# stm32H7_board_rev8_144_16.net
KiCad netlist of a schematic drawn in EAGLE
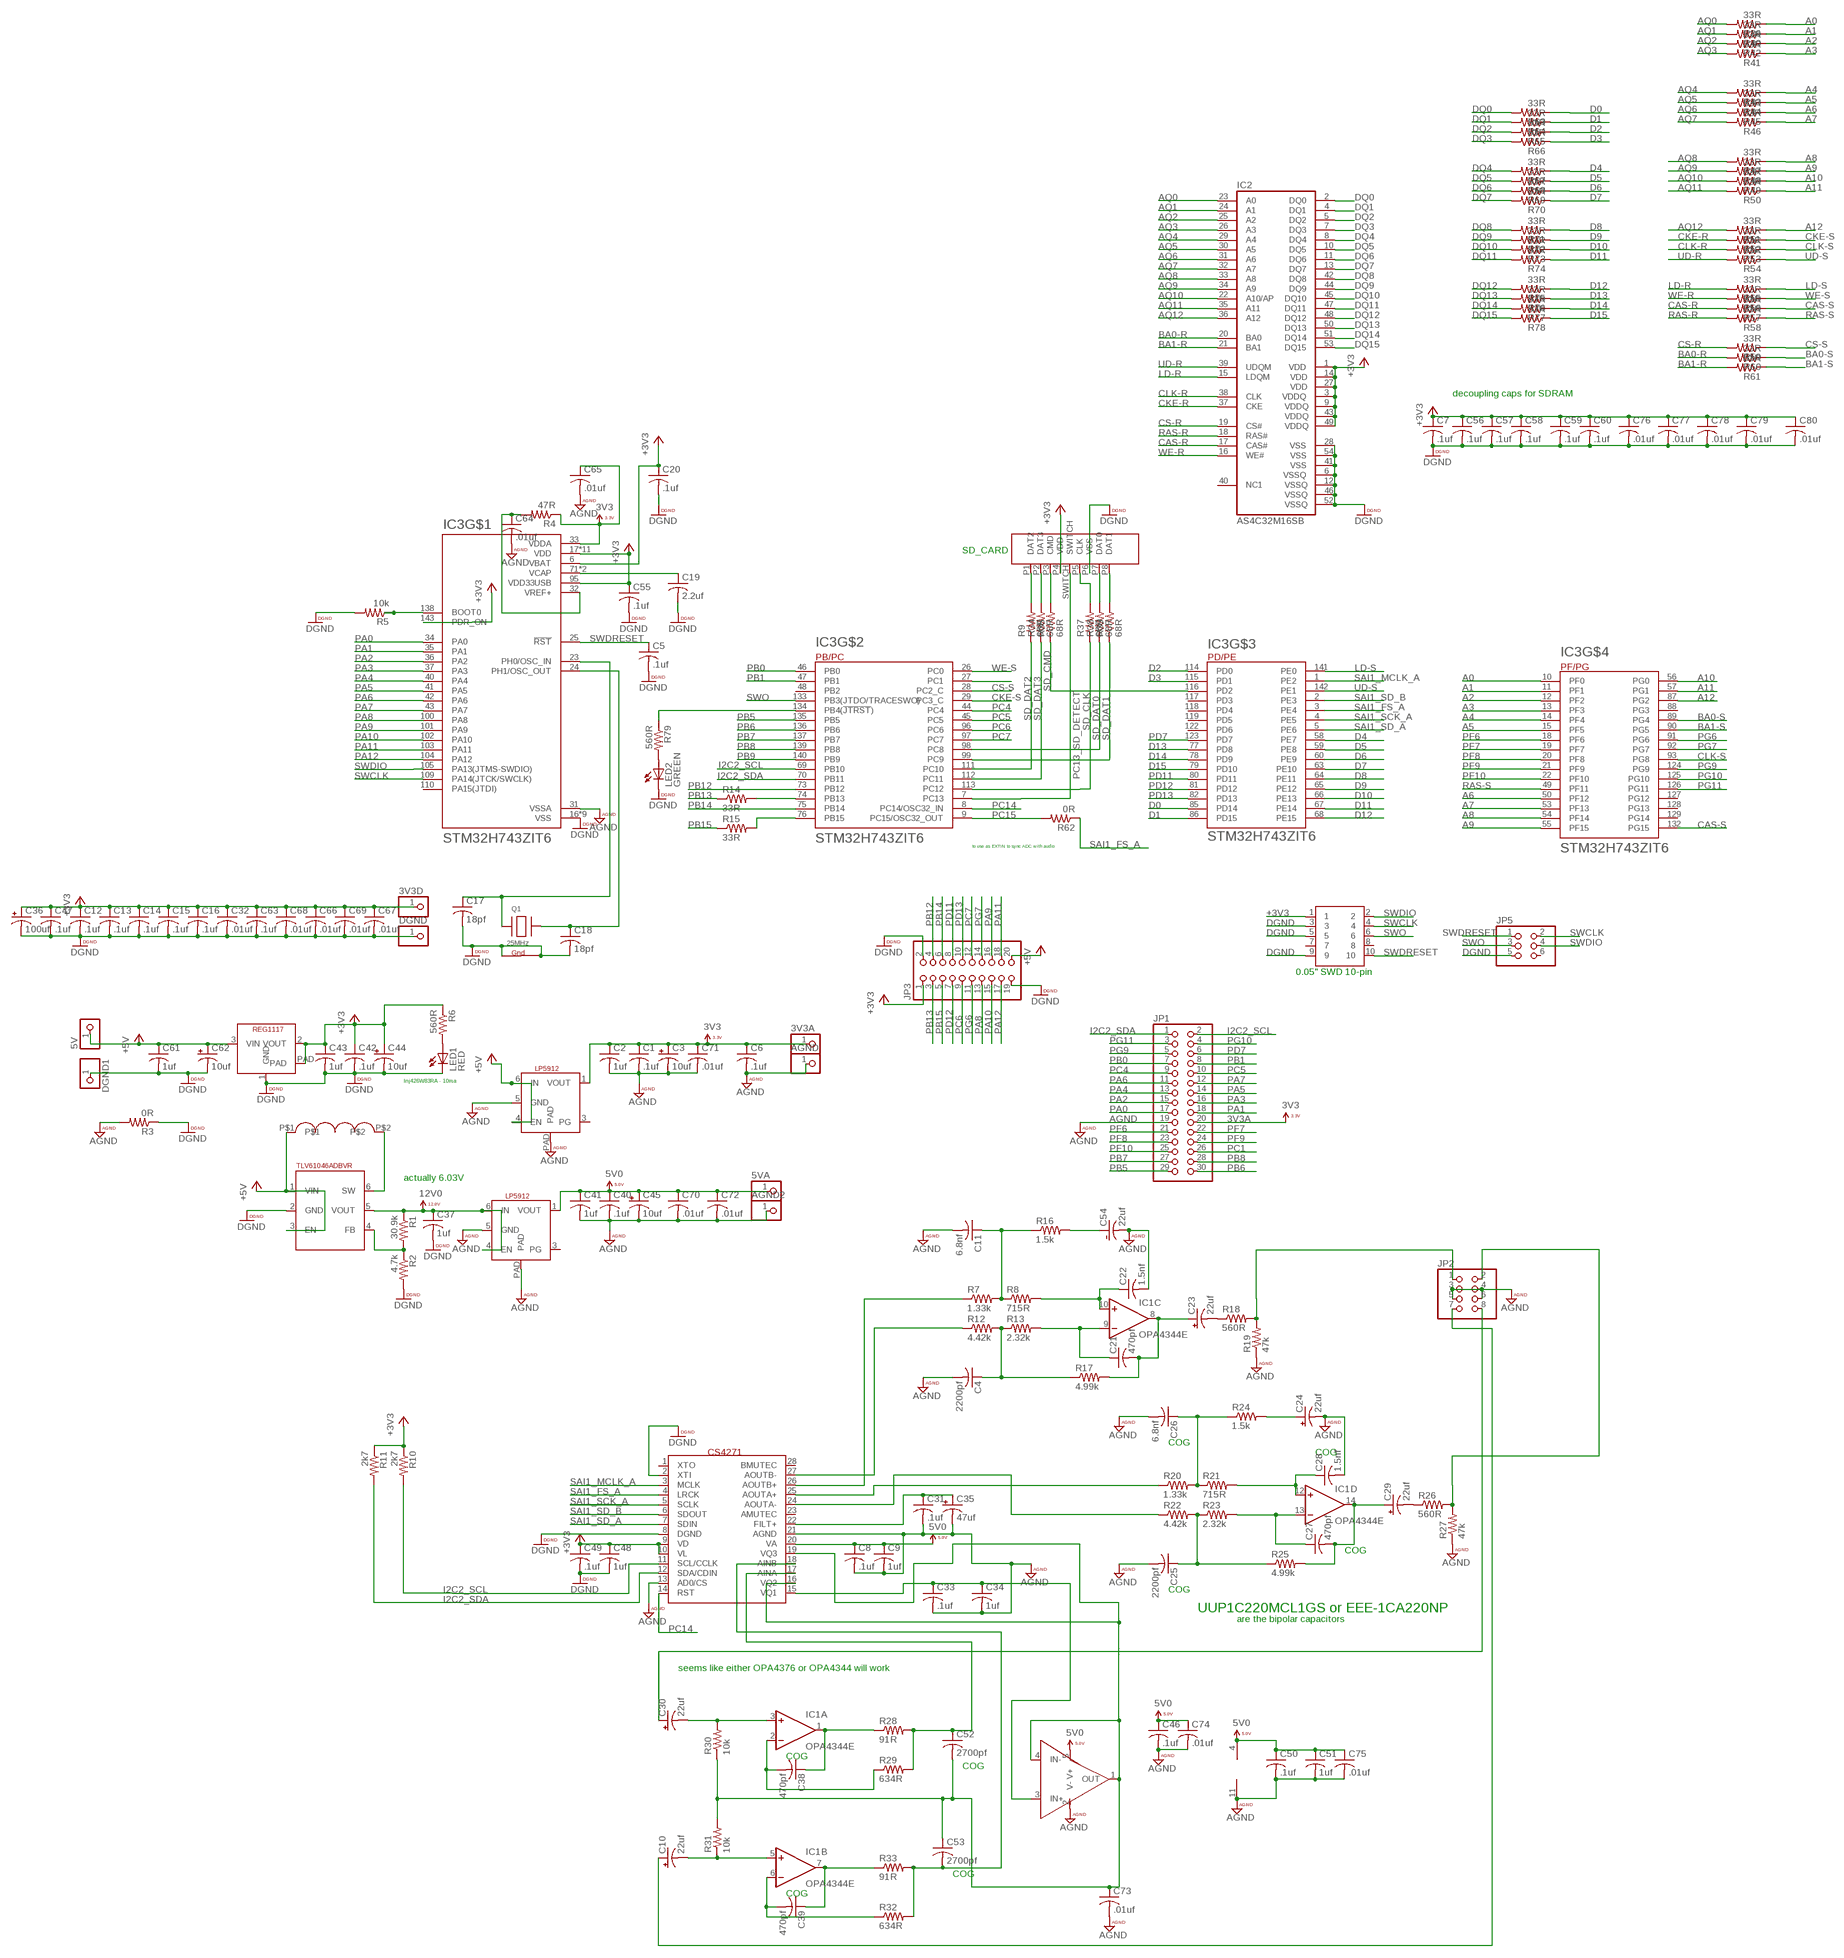
[diagram p0: schematic, sheet 1]

(export (version "E")
  (design (tool "Eeschema 10.0.6"))
  (components
    (comp (ref "3V3A")
      (value "PINHD-1X1")
      (footprint "eagle-import:1X01")
      (fields (field (name "PARTNO") "*DNP"))
      (libsource (lib "eagle-import") (part "PINHD-1X1"))
    )
    (comp (ref "3V3D")
      (value "PINHD-1X1")
      (footprint "eagle-import:1X01")
      (fields (field (name "PARTNO") "*DNP"))
      (libsource (lib "eagle-import") (part "PINHD-1X1"))
    )
    (comp (ref "5V")
      (value "PINHD-1X1")
      (footprint "eagle-import:1X01")
      (fields (field (name "PARTNO") "*DNP"))
      (libsource (lib "eagle-import") (part "PINHD-1X1"))
    )
    (comp (ref "5VA")
      (value "PINHD-1X1")
      (footprint "eagle-import:1X01")
      (fields (field (name "PARTNO") "*DNP"))
      (libsource (lib "eagle-import") (part "PINHD-1X1"))
    )
    (comp (ref "AGND")
      (value "PINHD-1X1")
      (footprint "eagle-import:1X01")
      (fields (field (name "PARTNO") "*DNP"))
      (libsource (lib "eagle-import") (part "PINHD-1X1"))
    )
    (comp (ref "AGND2")
      (value "PINHD-1X1")
      (footprint "eagle-import:1X01")
      (fields (field (name "PARTNO") "*DNP"))
      (libsource (lib "eagle-import") (part "PINHD-1X1"))
    )
    (comp (ref "C1")
      (value ".1uf")
      (footprint "eagle-import:C0603")
      (fields (field (name "PARTNO") "CC0603KRX7R8BB104"))
      (libsource (lib "eagle-import") (part "rcl_C-USC0603"))
    )
    (comp (ref "C2")
      (value "1uf")
      (footprint "eagle-import:C1206")
      (fields (field (name "PARTNO") "C3216X7R1E105K085AA"))
      (libsource (lib "eagle-import") (part "rcl_C-USC1206"))
    )
    (comp (ref "C3")
      (value "10uf")
      (footprint "eagle-import:SMC_B")
      (fields (field (name "PARTNO") "TAJB106K025RNJ"))
      (libsource (lib "eagle-import") (part "CPOL-USSMCB"))
    )
    (comp (ref "C4")
      (value "2200pf")
      (footprint "eagle-import:C0603")
      (fields (field (name "PARTNO") "CC0603JRNPO9BN221"))
      (libsource (lib "eagle-import") (part "rcl_C-USC0603"))
    )
    (comp (ref "C5")
      (value ".1uf")
      (footprint "eagle-import:C0402")
      (fields (field (name "PARTNO") "CC0402KRX7R8BB104"))
      (libsource (lib "eagle-import") (part "rcl_C-USC0402"))
    )
    (comp (ref "C6")
      (value ".1uf")
      (footprint "eagle-import:C0402")
      (fields (field (name "PARTNO") "CC0402KRX7R8BB104"))
      (libsource (lib "eagle-import") (part "rcl_C-USC0402"))
    )
    (comp (ref "C7")
      (value ".1uf")
      (footprint "eagle-import:C0402")
      (fields (field (name "PARTNO") "CC0402KRX7R8BB104"))
      (libsource (lib "eagle-import") (part "rcl_C-USC0402"))
    )
    (comp (ref "C8")
      (value ".1uf")
      (footprint "eagle-import:C0603")
      (fields (field (name "PARTNO") "CC0603KRX7R8BB104"))
      (libsource (lib "eagle-import") (part "rcl_C-USC0603"))
    )
    (comp (ref "C9")
      (value "1uf")
      (footprint "eagle-import:C1206")
      (fields (field (name "PARTNO") "C3216X7R1E105K085AA"))
      (libsource (lib "eagle-import") (part "rcl_C-USC1206"))
    )
    (comp (ref "C10")
      (value "22uf")
      (footprint "eagle-import:PANASONIC_D")
      (fields (field (name "PARTNO") "EEE-1CA220NP"))
      (libsource (lib "eagle-import") (part "CPOL-USD"))
    )
    (comp (ref "C11")
      (value "6.8nf")
      (footprint "eagle-import:C0603")
      (fields (field (name "PARTNO") "C0603C682J5GACTU"))
      (libsource (lib "eagle-import") (part "rcl_C-USC0603"))
    )
    (comp (ref "C12")
      (value ".1uf")
      (footprint "eagle-import:C0402")
      (fields (field (name "PARTNO") "CC0402KRX7R8BB104"))
      (libsource (lib "eagle-import") (part "rcl_C-USC0402"))
    )
    (comp (ref "C13")
      (value ".1uf")
      (footprint "eagle-import:C0402")
      (fields (field (name "PARTNO") "CC0402KRX7R8BB104"))
      (libsource (lib "eagle-import") (part "rcl_C-USC0402"))
    )
    (comp (ref "C14")
      (value ".1uf")
      (footprint "eagle-import:C0402")
      (fields (field (name "PARTNO") "CC0402KRX7R8BB104"))
      (libsource (lib "eagle-import") (part "rcl_C-USC0402"))
    )
    (comp (ref "C15")
      (value ".1uf")
      (footprint "eagle-import:C0402")
      (fields (field (name "PARTNO") "CC0402KRX7R8BB104"))
      (libsource (lib "eagle-import") (part "rcl_C-USC0402"))
    )
    (comp (ref "C16")
      (value ".1uf")
      (footprint "eagle-import:C0402")
      (fields (field (name "PARTNO") "CC0402KRX7R8BB104"))
      (libsource (lib "eagle-import") (part "rcl_C-USC0402"))
    )
    (comp (ref "C17")
      (value "18pf")
      (footprint "eagle-import:C0603")
      (fields (field (name "PARTNO") "CL10C180JB8NNNC"))
      (libsource (lib "eagle-import") (part "rcl_C-USC0603"))
    )
    (comp (ref "C18")
      (value "18pf")
      (footprint "eagle-import:C0603")
      (fields (field (name "PARTNO") "CL10C180JB8NNNC"))
      (libsource (lib "eagle-import") (part "rcl_C-USC0603"))
    )
    (comp (ref "C19")
      (value "2.2uf")
      (footprint "eagle-import:C1206")
      (fields (field (name "PARTNO") "T491A225K020AT"))
      (libsource (lib "eagle-import") (part "C-USC1206"))
    )
    (comp (ref "C20")
      (value ".1uf")
      (footprint "eagle-import:C0402")
      (fields (field (name "PARTNO") "CC0402KRX7R8BB104"))
      (libsource (lib "eagle-import") (part "rcl_C-USC0402"))
    )
    (comp (ref "C21")
      (value "470pf")
      (footprint "eagle-import:C0603")
      (fields (field (name "PARTNO") "CC0603JRNPO9BN471"))
      (libsource (lib "eagle-import") (part "rcl_C-USC0603"))
    )
    (comp (ref "C22")
      (value "1.5nf")
      (footprint "eagle-import:C0603")
      (fields (field (name "PARTNO") "C0603C152J5GACTU"))
      (libsource (lib "eagle-import") (part "rcl_C-USC0603"))
    )
    (comp (ref "C23")
      (value "22uf")
      (footprint "eagle-import:PANASONIC_D")
      (fields (field (name "PARTNO") "EEE-1CA220NP"))
      (libsource (lib "eagle-import") (part "CPOL-USD"))
    )
    (comp (ref "C24")
      (value "22uf")
      (footprint "eagle-import:PANASONIC_D")
      (fields (field (name "PARTNO") "EEE-1CA220NP"))
      (libsource (lib "eagle-import") (part "CPOL-USD"))
    )
    (comp (ref "C25")
      (value "2200pf")
      (footprint "eagle-import:C0603")
      (fields (field (name "PARTNO") "CC0603JRNPO9BN221"))
      (libsource (lib "eagle-import") (part "rcl_C-USC0603"))
    )
    (comp (ref "C26")
      (value "6.8nf")
      (footprint "eagle-import:C0603")
      (fields (field (name "PARTNO") "C0603C682J5GACTU"))
      (libsource (lib "eagle-import") (part "rcl_C-USC0603"))
    )
    (comp (ref "C27")
      (value "470pf")
      (footprint "eagle-import:C0603")
      (fields (field (name "PARTNO") "CC0603JRNPO9BN471"))
      (libsource (lib "eagle-import") (part "rcl_C-USC0603"))
    )
    (comp (ref "C28")
      (value "1.5nf")
      (footprint "eagle-import:C0603")
      (fields (field (name "PARTNO") "C0603C152J5GACTU"))
      (libsource (lib "eagle-import") (part "rcl_C-USC0603"))
    )
    (comp (ref "C29")
      (value "22uf")
      (footprint "eagle-import:PANASONIC_D")
      (fields (field (name "PARTNO") "EEE-1CA220NP"))
      (libsource (lib "eagle-import") (part "CPOL-USD"))
    )
    (comp (ref "C30")
      (value "22uf")
      (footprint "eagle-import:PANASONIC_D")
      (fields (field (name "PARTNO") "EEE-1CA220NP"))
      (libsource (lib "eagle-import") (part "CPOL-USD"))
    )
    (comp (ref "C31")
      (value ".1uf")
      (footprint "eagle-import:C0603")
      (fields (field (name "PARTNO") "CC0603KRX7R8BB104"))
      (libsource (lib "eagle-import") (part "rcl_C-USC0603"))
    )
    (comp (ref "C32")
      (value ".01uf")
      (footprint "eagle-import:C0402")
      (fields (field (name "PARTNO") "CC0402KRX7R8BB103"))
      (libsource (lib "eagle-import") (part "rcl_C-USC0402"))
    )
    (comp (ref "C33")
      (value ".1uf")
      (footprint "eagle-import:C0603")
      (fields (field (name "PARTNO") "CC0603KRX7R8BB104"))
      (libsource (lib "eagle-import") (part "rcl_C-USC0603"))
    )
    (comp (ref "C34")
      (value "1uf")
      (footprint "eagle-import:C1206")
      (fields (field (name "PARTNO") "C3216X7R1E105K085AA"))
      (libsource (lib "eagle-import") (part "rcl_C-USC1206"))
    )
    (comp (ref "C35")
      (value "47uf")
      (footprint "eagle-import:PANASONIC_D")
      (fields (field (name "PARTNO") "EEE-1CA470AP"))
      (libsource (lib "eagle-import") (part "CPOL-USD"))
    )
    (comp (ref "C36")
      (value "100uf")
      (footprint "eagle-import:PANASONIC_E")
      (fields (field (name "PARTNO") "EEE-1CA101AP"))
      (libsource (lib "eagle-import") (part "CPOL-USE"))
    )
    (comp (ref "C37")
      (value "1uf")
      (footprint "eagle-import:C1206")
      (fields (field (name "PARTNO") "C3216X7R1E105K085AA"))
      (libsource (lib "eagle-import") (part "rcl_C-USC1206"))
    )
    (comp (ref "C38")
      (value "470pf")
      (footprint "eagle-import:C0603")
      (fields (field (name "PARTNO") "CC0603JRNPO9BN471"))
      (libsource (lib "eagle-import") (part "rcl_C-USC0603"))
    )
    (comp (ref "C39")
      (value "470pf")
      (footprint "eagle-import:C0603")
      (fields (field (name "PARTNO") "CC0603JRNPO9BN471"))
      (libsource (lib "eagle-import") (part "rcl_C-USC0603"))
    )
    (comp (ref "C40")
      (value ".1uf")
      (footprint "eagle-import:C0603")
      (fields (field (name "PARTNO") "CC0603KRX7R8BB104"))
      (libsource (lib "eagle-import") (part "rcl_C-USC0603"))
    )
    (comp (ref "C41")
      (value "1uf")
      (footprint "eagle-import:C1206")
      (fields (field (name "PARTNO") "C3216X7R1E105K085AA"))
      (libsource (lib "eagle-import") (part "rcl_C-USC1206"))
    )
    (comp (ref "C42")
      (value ".1uf")
      (footprint "eagle-import:C0603")
      (fields (field (name "PARTNO") "CC0603KRX7R8BB104"))
      (libsource (lib "eagle-import") (part "rcl_C-USC0603"))
    )
    (comp (ref "C43")
      (value "1uf")
      (footprint "eagle-import:C1206")
      (fields (field (name "PARTNO") "C3216X7R1E105K085AA"))
      (libsource (lib "eagle-import") (part "rcl_C-USC1206"))
    )
    (comp (ref "C44")
      (value "10uf")
      (footprint "eagle-import:SMC_B")
      (fields (field (name "PARTNO") "TAJB106K025RNJ"))
      (libsource (lib "eagle-import") (part "CPOL-USSMCB"))
    )
    (comp (ref "C45")
      (value "10uf")
      (footprint "eagle-import:SMC_B")
      (fields (field (name "PARTNO") "TAJB106K025RNJ"))
      (libsource (lib "eagle-import") (part "CPOL-USSMCB"))
    )
    (comp (ref "C46")
      (value ".1uf")
      (footprint "eagle-import:C0603")
      (fields (field (name "PARTNO") "CC0603KRX7R8BB104"))
      (libsource (lib "eagle-import") (part "rcl_C-USC0603"))
    )
    (comp (ref "C47")
      (value ".1uf")
      (footprint "eagle-import:C0402")
      (fields (field (name "PARTNO") "CC0402KRX7R8BB104"))
      (libsource (lib "eagle-import") (part "rcl_C-USC0402"))
    )
    (comp (ref "C48")
      (value "1uf")
      (footprint "eagle-import:C1206")
      (fields (field (name "PARTNO") "C3216X7R1E105K085AA"))
      (libsource (lib "eagle-import") (part "rcl_C-USC1206"))
    )
    (comp (ref "C49")
      (value ".1uf")
      (footprint "eagle-import:C0603")
      (fields (field (name "PARTNO") "CC0603KRX7R8BB104"))
      (libsource (lib "eagle-import") (part "rcl_C-USC0603"))
    )
    (comp (ref "C50")
      (value ".1uf")
      (footprint "eagle-import:C0603")
      (fields (field (name "PARTNO") "CC0603KRX7R8BB104"))
      (libsource (lib "eagle-import") (part "rcl_C-USC0603"))
    )
    (comp (ref "C51")
      (value "1uf")
      (footprint "eagle-import:C1206")
      (fields (field (name "PARTNO") "C3216X7R1E105K085AA"))
      (libsource (lib "eagle-import") (part "rcl_C-USC1206"))
    )
    (comp (ref "C52")
      (value "2700pf")
      (footprint "eagle-import:C0603")
      (fields (field (name "PARTNO") "C0603C272J5GACTU"))
      (libsource (lib "eagle-import") (part "rcl_C-USC0603"))
    )
    (comp (ref "C53")
      (value "2700pf")
      (footprint "eagle-import:C0603")
      (fields (field (name "PARTNO") "C0603C272J5GACTU"))
      (libsource (lib "eagle-import") (part "rcl_C-USC0603"))
    )
    (comp (ref "C54")
      (value "22uf")
      (footprint "eagle-import:PANASONIC_D")
      (fields (field (name "PARTNO") "EEE-1CA220NP"))
      (libsource (lib "eagle-import") (part "CPOL-USD"))
    )
    (comp (ref "C55")
      (value ".1uf")
      (footprint "eagle-import:C0402")
      (fields (field (name "PARTNO") "CC0402KRX7R8BB104"))
      (libsource (lib "eagle-import") (part "rcl_C-USC0402"))
    )
    (comp (ref "C56")
      (value ".1uf")
      (footprint "eagle-import:C0402")
      (fields (field (name "PARTNO") "CC0402KRX7R8BB104"))
      (libsource (lib "eagle-import") (part "rcl_C-USC0402"))
    )
    (comp (ref "C57")
      (value ".1uf")
      (footprint "eagle-import:C0402")
      (fields (field (name "PARTNO") "CC0402KRX7R8BB104"))
      (libsource (lib "eagle-import") (part "rcl_C-USC0402"))
    )
    (comp (ref "C58")
      (value ".1uf")
      (footprint "eagle-import:C0402")
      (fields (field (name "PARTNO") "CC0402KRX7R8BB104"))
      (libsource (lib "eagle-import") (part "rcl_C-USC0402"))
    )
    (comp (ref "C59")
      (value ".1uf")
      (footprint "eagle-import:C0402")
      (fields (field (name "PARTNO") "CC0402KRX7R8BB104"))
      (libsource (lib "eagle-import") (part "rcl_C-USC0402"))
    )
    (comp (ref "C60")
      (value ".1uf")
      (footprint "eagle-import:C0402")
      (fields (field (name "PARTNO") "CC0402KRX7R8BB104"))
      (libsource (lib "eagle-import") (part "rcl_C-USC0402"))
    )
    (comp (ref "C61")
      (value "1uf")
      (footprint "eagle-import:C1206")
      (fields (field (name "PARTNO") "C3216X7R1E105K085AA"))
      (libsource (lib "eagle-import") (part "rcl_C-USC1206"))
    )
    (comp (ref "C62")
      (value "10uf")
      (footprint "eagle-import:SMC_B")
      (fields (field (name "PARTNO") "TAJB106K025RNJ"))
      (libsource (lib "eagle-import") (part "CPOL-USSMCB"))
    )
    (comp (ref "C63")
      (value ".1uf")
      (footprint "eagle-import:C0402")
      (fields (field (name "PARTNO") "CC0402KRX7R8BB104"))
      (libsource (lib "eagle-import") (part "rcl_C-USC0402"))
    )
    (comp (ref "C64")
      (value ".01uf")
      (footprint "eagle-import:C0402")
      (fields (field (name "PARTNO") "CC0402KRX7R8BB103"))
      (libsource (lib "eagle-import") (part "rcl_C-USC0402"))
    )
    (comp (ref "C65")
      (value ".01uf")
      (footprint "eagle-import:C0402")
      (fields (field (name "PARTNO") "CC0402KRX7R8BB103"))
      (libsource (lib "eagle-import") (part "rcl_C-USC0402"))
    )
    (comp (ref "C66")
      (value ".01uf")
      (footprint "eagle-import:C0201")
      (fields (field (name "PARTNO") "TMK063B7103KP-F"))
      (libsource (lib "eagle-import") (part "C-USC0201"))
    )
    (comp (ref "C67")
      (value ".01uf")
      (footprint "eagle-import:C0201")
      (fields (field (name "PARTNO") "TMK063B7103KP-F"))
      (libsource (lib "eagle-import") (part "C-USC0201"))
    )
    (comp (ref "C68")
      (value ".01uf")
      (footprint "eagle-import:C0201")
      (fields (field (name "PARTNO") "TMK063B7103KP-F"))
      (libsource (lib "eagle-import") (part "C-USC0201"))
    )
    (comp (ref "C69")
      (value ".01uf")
      (footprint "eagle-import:C0201")
      (fields (field (name "PARTNO") "TMK063B7103KP-F"))
      (libsource (lib "eagle-import") (part "C-USC0201"))
    )
    (comp (ref "C70")
      (value ".01uf")
      (footprint "eagle-import:C0201")
      (fields (field (name "PARTNO") "TMK063B7103KP-F"))
      (libsource (lib "eagle-import") (part "C-USC0201"))
    )
    (comp (ref "C71")
      (value ".01uf")
      (footprint "eagle-import:C0201")
      (fields (field (name "PARTNO") "TMK063B7103KP-F"))
      (libsource (lib "eagle-import") (part "C-USC0201"))
    )
    (comp (ref "C72")
      (value ".01uf")
      (footprint "eagle-import:C0201")
      (fields (field (name "PARTNO") "TMK063B7103KP-F"))
      (libsource (lib "eagle-import") (part "C-USC0201"))
    )
    (comp (ref "C73")
      (value ".01uf")
      (footprint "eagle-import:C0201")
      (fields (field (name "PARTNO") "TMK063B7103KP-F"))
      (libsource (lib "eagle-import") (part "C-USC0201"))
    )
    (comp (ref "C74")
      (value ".01uf")
      (footprint "eagle-import:C0201")
      (fields (field (name "PARTNO") "TMK063B7103KP-F"))
      (libsource (lib "eagle-import") (part "C-USC0201"))
    )
    (comp (ref "C75")
      (value ".01uf")
      (footprint "eagle-import:C0201")
      (fields (field (name "PARTNO") "TMK063B7103KP-F"))
      (libsource (lib "eagle-import") (part "C-USC0201"))
    )
    (comp (ref "C76")
      (value ".01uf")
      (footprint "eagle-import:C0201")
      (fields (field (name "PARTNO") "TMK063B7103KP-F"))
      (libsource (lib "eagle-import") (part "C-USC0201"))
    )
    (comp (ref "C77")
      (value ".01uf")
      (footprint "eagle-import:C0201")
      (fields (field (name "PARTNO") "TMK063B7103KP-F"))
      (libsource (lib "eagle-import") (part "C-USC0201"))
    )
    (comp (ref "C78")
      (value ".01uf")
      (footprint "eagle-import:C0201")
      (fields (field (name "PARTNO") "TMK063B7103KP-F"))
      (libsource (lib "eagle-import") (part "C-USC0201"))
    )
    (comp (ref "C79")
      (value ".01uf")
      (footprint "eagle-import:C0201")
      (fields (field (name "PARTNO") "TMK063B7103KP-F"))
      (libsource (lib "eagle-import") (part "C-USC0201"))
    )
    (comp (ref "C80")
      (value ".01uf")
      (footprint "eagle-import:C0201")
      (fields (field (name "PARTNO") "TMK063B7103KP-F"))
      (libsource (lib "eagle-import") (part "C-USC0201"))
    )
    (comp (ref "DGND")
      (value "PINHD-1X1")
      (footprint "eagle-import:1X01")
      (fields (field (name "PARTNO") "*DNP"))
      (libsource (lib "eagle-import") (part "PINHD-1X1"))
    )
    (comp (ref "DGND1")
      (value "PINHD-1X1")
      (footprint "eagle-import:1X01")
      (fields (field (name "PARTNO") "*DNP"))
      (libsource (lib "eagle-import") (part "PINHD-1X1"))
    )
    (comp (ref "IC1")
      (value "OPA4344E")
      (footprint "eagle-import:TSSOP14")
      (fields (field (name "PARTNO") "ADA4807-4ARUZ-R7"))
      (libsource (lib "eagle-import") (part "OPA4E344"))
    )
    (comp (ref "IC2")
      (value "AS4C32M16SB")
      (footprint "eagle-import:TSOP54")
      (fields (field (name "PARTNO") "AS4C16M16SA-7TCN"))
      (libsource (lib "eagle-import") (part "AS4C32M16SB"))
    )
    (comp (ref "IC3")
      (value "STM32H743ZIT6")
      (footprint "eagle-import:QFP50P2200X2200X160-144N")
      (fields (field (name "MF") "STMicroelectronics") (field (name "PARTNO") "STM32H743ZIT6"))
      (libsource (lib "eagle-import") (part "STM32H743ZIT6"))
    )
    (comp (ref "IC4")
      (value "REG1117")
      (footprint "eagle-import:SOT223")
      (fields (field (name "PARTNO") "LM1117IMPX-3.3/NOPB"))
      (libsource (lib "eagle-import") (part "REG1117"))
    )
    (comp (ref "IC5")
      (value "CS4271")
      (footprint "eagle-import:TSSOP28")
      (fields (field (name "PARTNO") "CS4271-CZZ"))
      (libsource (lib "eagle-import") (part "CS4271"))
    )
    (comp (ref "IC6")
      (value "TLV170")
      (footprint "eagle-import:SOT23-5L")
      (fields (field (name "PARTNO") "TLV170IDBVT"))
      (libsource (lib "eagle-import") (part "TLV170"))
    )
    (comp (ref "IC7")
      (value "TLV61046ADBVR")
      (footprint "eagle-import:SOT23-6")
      (libsource (lib "eagle-import") (part "TLV61046ADBVR"))
    )
    (comp (ref "IC8")
      (value "LP5912")
      (footprint "eagle-import:6-WSON")
      (fields (field (name "PARTNO") "LP5912-5.0DRVR"))
      (libsource (lib "eagle-import") (part "LP5912"))
    )
    (comp (ref "IC9")
      (value "LP5912")
      (footprint "eagle-import:6-WSON")
      (fields (field (name "PARTNO") "LP5912-3.3DRVT"))
      (libsource (lib "eagle-import") (part "LP5912"))
    )
    (comp (ref "JP1")
      (value "PINHD-2X15")
      (footprint "eagle-import:2X15")
      (fields (field (name "PARTNO") "76342-315LF"))
      (libsource (lib "eagle-import") (part "PINHD-2X15"))
    )
    (comp (ref "JP2")
      (value "PINHD-2X4")
      (footprint "eagle-import:2X04")
      (fields (field (name "PARTNO") "76342-304LF"))
      (libsource (lib "eagle-import") (part "PINHD-2X4"))
    )
    (comp (ref "JP3")
      (value "PINHD-2X10")
      (footprint "eagle-import:2X10")
      (fields (field (name "PARTNO") "76342-310LF"))
      (libsource (lib "eagle-import") (part "PINHD-2X10"))
    )
    (comp (ref "JP5")
      (value "PINHD-2X3")
      (footprint "eagle-import:2X03")
      (fields (field (name "PARTNO") "*DNP"))
      (libsource (lib "eagle-import") (part "PINHD-2X3"))
    )
    (comp (ref "L1")
      (value "74438336100")
      (footprint "eagle-import:1212")
      (libsource (lib "eagle-import") (part "74438336100"))
    )
    (comp (ref "LED1")
      (value "RED")
      (footprint "eagle-import:CHIP-LED0603")
      (fields (field (name "PARTNO") "5973006507F"))
      (libsource (lib "eagle-import") (part "LEDCHIP-LED0603"))
    )
    (comp (ref "LED2")
      (value "GREEN")
      (footprint "eagle-import:CHIP-LED0603")
      (fields (field (name "PARTNO") "5973506507F"))
      (libsource (lib "eagle-import") (part "LEDCHIP-LED0603"))
    )
    (comp (ref "Q1")
      (value "25MHz")
      (footprint "eagle-import:NX3225")
      (fields (field (name "PARTNO") "7M-25.000MAAJ-T"))
      (libsource (lib "eagle-import") (part "XTAL-4-3225"))
    )
    (comp (ref "R1")
      (value "30.9k")
      (footprint "eagle-import:R0603")
      (fields (field (name "PARTNO") "RT0603BRD0730K9L"))
      (libsource (lib "eagle-import") (part "resistor_R-US_R0603"))
    )
    (comp (ref "R2")
      (value "4.7k")
      (footprint "eagle-import:R0603")
      (fields (field (name "PARTNO") "CRCW06034K70FKEAHP"))
      (libsource (lib "eagle-import") (part "resistor_R-US_R0603"))
    )
    (comp (ref "R3")
      (value "0R")
      (footprint "eagle-import:R0603")
      (fields (field (name "PARTNO") "RCS06030000Z0EA"))
      (libsource (lib "eagle-import") (part "resistor_R-US_R0603"))
    )
    (comp (ref "R4")
      (value "47R")
      (footprint "eagle-import:R0603")
      (fields (field (name "PARTNO") "ESR03EZPJ470"))
      (libsource (lib "eagle-import") (part "resistor_R-US_R0603"))
    )
    (comp (ref "R5")
      (value "10k")
      (footprint "eagle-import:R0402")
      (fields (field (name "PARTNO") "RC0402FR-0710KL"))
      (libsource (lib "eagle-import") (part "resistor_R-US_R0402"))
    )
    (comp (ref "R6")
      (value "560R")
      (footprint "eagle-import:R0603")
      (fields (field (name "PARTNO") "ESR03EZPF5600"))
      (libsource (lib "eagle-import") (part "resistor_R-US_R0603"))
    )
    (comp (ref "R7")
      (value "1.33k")
      (footprint "eagle-import:R0603")
      (fields (field (name "PARTNO") "RT0603BRD071K33L"))
      (libsource (lib "eagle-import") (part "resistor_R-US_R0603"))
    )
    (comp (ref "R8")
      (value "715R")
      (footprint "eagle-import:R0603")
      (fields (field (name "PARTNO") "RC0603FR-07715RL"))
      (libsource (lib "eagle-import") (part "resistor_R-US_R0603"))
    )
    (comp (ref "R9")
      (value "68R")
      (footprint "eagle-import:R0201")
      (fields (field (name "PARTNO") "RC0201FR-0768RL"))
      (libsource (lib "eagle-import") (part "R-US_R0201"))
    )
    (comp (ref "R10")
      (value "2k7")
      (footprint "eagle-import:R0603")
      (fields (field (name "PARTNO") "RT0603BRD072K7L"))
      (libsource (lib "eagle-import") (part "resistor_R-US_R0603"))
    )
    (comp (ref "R11")
      (value "2k7")
      (footprint "eagle-import:R0603")
      (fields (field (name "PARTNO") "RT0603BRD072K7L"))
      (libsource (lib "eagle-import") (part "resistor_R-US_R0603"))
    )
    (comp (ref "R12")
      (value "4.42k")
      (footprint "eagle-import:R0603")
      (fields (field (name "PARTNO") "RT0603BRD074K42L"))
      (libsource (lib "eagle-import") (part "resistor_R-US_R0603"))
    )
    (comp (ref "R13")
      (value "2.32k")
      (footprint "eagle-import:R0603")
      (fields (field (name "PARTNO") "RT0603BRD072K32L"))
      (libsource (lib "eagle-import") (part "resistor_R-US_R0603"))
    )
    (comp (ref "R14")
      (value "33R")
      (footprint "eagle-import:R0402")
      (fields (field (name "PARTNO") "RC0402FR-0733RL"))
      (libsource (lib "eagle-import") (part "resistor_R-US_R0402"))
    )
    (comp (ref "R15")
      (value "33R")
      (footprint "eagle-import:R0402")
      (fields (field (name "PARTNO") "RC0402FR-0733RL"))
      (libsource (lib "eagle-import") (part "resistor_R-US_R0402"))
    )
    (comp (ref "R16")
      (value "1.5k")
      (footprint "eagle-import:R0603")
      (fields (field (name "PARTNO") "ESR03EZPJ152"))
      (libsource (lib "eagle-import") (part "resistor_R-US_R0603"))
    )
    (comp (ref "R17")
      (value "4.99k")
      (footprint "eagle-import:R0603")
      (fields (field (name "PARTNO") "RT0603BRD074K99L"))
      (libsource (lib "eagle-import") (part "resistor_R-US_R0603"))
    )
    (comp (ref "R18")
      (value "560R")
      (footprint "eagle-import:R0603")
      (fields (field (name "PARTNO") "ESR03EZPF5600"))
      (libsource (lib "eagle-import") (part "resistor_R-US_R0603"))
    )
    (comp (ref "R19")
      (value "47k")
      (footprint "eagle-import:R0603")
      (fields (field (name "PARTNO") "ESR03EZPJ473"))
      (libsource (lib "eagle-import") (part "resistor_R-US_R0603"))
    )
    (comp (ref "R20")
      (value "1.33k")
      (footprint "eagle-import:R0603")
      (fields (field (name "PARTNO") "RT0603BRD071K33L"))
      (libsource (lib "eagle-import") (part "resistor_R-US_R0603"))
    )
    (comp (ref "R21")
      (value "715R")
      (footprint "eagle-import:R0603")
      (fields (field (name "PARTNO") "RC0603FR-07715RL"))
      (libsource (lib "eagle-import") (part "resistor_R-US_R0603"))
    )
    (comp (ref "R22")
      (value "4.42k")
      (footprint "eagle-import:R0603")
      (fields (field (name "PARTNO") "RT0603BRD074K42L"))
      (libsource (lib "eagle-import") (part "resistor_R-US_R0603"))
    )
    (comp (ref "R23")
      (value "2.32k")
      (footprint "eagle-import:R0603")
      (fields (field (name "PARTNO") "RT0603BRD072K32L"))
      (libsource (lib "eagle-import") (part "resistor_R-US_R0603"))
    )
    (comp (ref "R24")
      (value "1.5k")
      (footprint "eagle-import:R0603")
      (fields (field (name "PARTNO") "ESR03EZPJ152"))
      (libsource (lib "eagle-import") (part "resistor_R-US_R0603"))
    )
    (comp (ref "R25")
      (value "4.99k")
      (footprint "eagle-import:R0603")
      (fields (field (name "PARTNO") "RT0603BRD074K99L"))
      (libsource (lib "eagle-import") (part "resistor_R-US_R0603"))
    )
    (comp (ref "R26")
      (value "560R")
      (footprint "eagle-import:R0603")
      (fields (field (name "PARTNO") "ESR03EZPF5600"))
      (libsource (lib "eagle-import") (part "resistor_R-US_R0603"))
    )
    (comp (ref "R27")
      (value "47k")
      (footprint "eagle-import:R0603")
      (fields (field (name "PARTNO") "ESR03EZPJ473"))
      (libsource (lib "eagle-import") (part "resistor_R-US_R0603"))
    )
    (comp (ref "R28")
      (value "91R")
      (footprint "eagle-import:R0603")
      (fields (field (name "PARTNO") "RC0603JR-0791RL"))
      (libsource (lib "eagle-import") (part "resistor_R-US_R0603"))
    )
    (comp (ref "R29")
      (value "634R")
      (footprint "eagle-import:R0603")
      (fields (field (name "PARTNO") "RC0603FR-07634RL"))
      (libsource (lib "eagle-import") (part "resistor_R-US_R0603"))
    )
    (comp (ref "R30")
      (value "10k")
      (footprint "eagle-import:R0603")
      (fields (field (name "PARTNO") "ESR03EZPF1002"))
      (libsource (lib "eagle-import") (part "resistor_R-US_R0603"))
    )
    (comp (ref "R31")
      (value "10k")
      (footprint "eagle-import:R0603")
      (fields (field (name "PARTNO") "ESR03EZPF1002"))
      (libsource (lib "eagle-import") (part "resistor_R-US_R0603"))
    )
    (comp (ref "R32")
      (value "634R")
      (footprint "eagle-import:R0603")
      (fields (field (name "PARTNO") "RC0603FR-07634RL"))
      (libsource (lib "eagle-import") (part "resistor_R-US_R0603"))
    )
    (comp (ref "R33")
      (value "91R")
      (footprint "eagle-import:R0603")
      (fields (field (name "PARTNO") "RC0603JR-0791RL"))
      (libsource (lib "eagle-import") (part "resistor_R-US_R0603"))
    )
    (comp (ref "R34")
      (value "68R")
      (footprint "eagle-import:R0201")
      (fields (field (name "PARTNO") "RC0201FR-0768RL"))
      (libsource (lib "eagle-import") (part "R-US_R0201"))
    )
    (comp (ref "R35")
      (value "68R")
      (footprint "eagle-import:R0201")
      (fields (field (name "PARTNO") "RC0201FR-0768RL"))
      (libsource (lib "eagle-import") (part "R-US_R0201"))
    )
    (comp (ref "R36")
      (value "33R")
      (footprint "eagle-import:R0201")
      (fields (field (name "PARTNO") "RC0201FR-0733RL"))
      (libsource (lib "eagle-import") (part "R-US_R0201"))
    )
    (comp (ref "R37")
      (value "68R")
      (footprint "eagle-import:R0201")
      (fields (field (name "PARTNO") "RC0201FR-0768RL"))
      (libsource (lib "eagle-import") (part "R-US_R0201"))
    )
    (comp (ref "R38")
      (value "68R")
      (footprint "eagle-import:R0201")
      (fields (field (name "PARTNO") "RC0201FR-0768RL"))
      (libsource (lib "eagle-import") (part "R-US_R0201"))
    )
    (comp (ref "R39")
      (value "68R")
      (footprint "eagle-import:R0201")
      (fields (field (name "PARTNO") "RC0201FR-0768RL"))
      (libsource (lib "eagle-import") (part "R-US_R0201"))
    )
    (comp (ref "R40")
      (value "33R")
      (footprint "eagle-import:R0201")
      (fields (field (name "PARTNO") "RC0201FR-0733RL"))
      (libsource (lib "eagle-import") (part "R-US_R0201"))
    )
    (comp (ref "R41")
      (value "33R")
      (footprint "eagle-import:R0201")
      (fields (field (name "PARTNO") "RC0201FR-0733RL"))
      (libsource (lib "eagle-import") (part "R-US_R0201"))
    )
    (comp (ref "R42")
      (value "33R")
      (footprint "eagle-import:R0201")
      (fields (field (name "PARTNO") "RC0201FR-0733RL"))
      (libsource (lib "eagle-import") (part "R-US_R0201"))
    )
    (comp (ref "R43")
      (value "33R")
      (footprint "eagle-import:R0201")
      (fields (field (name "PARTNO") "RC0201FR-0733RL"))
      (libsource (lib "eagle-import") (part "R-US_R0201"))
    )
    (comp (ref "R44")
      (value "33R")
      (footprint "eagle-import:R0201")
      (fields (field (name "PARTNO") "RC0201FR-0733RL"))
      (libsource (lib "eagle-import") (part "R-US_R0201"))
    )
    (comp (ref "R45")
      (value "33R")
      (footprint "eagle-import:R0201")
      (fields (field (name "PARTNO") "RC0201FR-0733RL"))
      (libsource (lib "eagle-import") (part "R-US_R0201"))
    )
    (comp (ref "R46")
      (value "33R")
      (footprint "eagle-import:R0201")
      (fields (field (name "PARTNO") "RC0201FR-0733RL"))
      (libsource (lib "eagle-import") (part "R-US_R0201"))
    )
    (comp (ref "R47")
      (value "33R")
      (footprint "eagle-import:R0201")
      (fields (field (name "PARTNO") "RC0201FR-0733RL"))
      (libsource (lib "eagle-import") (part "R-US_R0201"))
    )
    (comp (ref "R48")
      (value "33R")
      (footprint "eagle-import:R0201")
      (fields (field (name "PARTNO") "RC0201FR-0733RL"))
      (libsource (lib "eagle-import") (part "R-US_R0201"))
    )
    (comp (ref "R49")
      (value "33R")
      (footprint "eagle-import:R0201")
      (fields (field (name "PARTNO") "RC0201FR-0733RL"))
      (libsource (lib "eagle-import") (part "R-US_R0201"))
    )
    (comp (ref "R50")
      (value "33R")
      (footprint "eagle-import:R0201")
      (fields (field (name "PARTNO") "RC0201FR-0733RL"))
      (libsource (lib "eagle-import") (part "R-US_R0201"))
    )
    (comp (ref "R51")
      (value "33R")
      (footprint "eagle-import:R0201")
      (fields (field (name "PARTNO") "RC0201FR-0733RL"))
      (libsource (lib "eagle-import") (part "R-US_R0201"))
    )
    (comp (ref "R52")
      (value "33R")
      (footprint "eagle-import:R0201")
      (fields (field (name "PARTNO") "RC0201FR-0733RL"))
      (libsource (lib "eagle-import") (part "R-US_R0201"))
    )
    (comp (ref "R53")
      (value "33R")
      (footprint "eagle-import:R0201")
      (fields (field (name "PARTNO") "RC0201FR-0733RL"))
      (libsource (lib "eagle-import") (part "R-US_R0201"))
    )
    (comp (ref "R54")
      (value "33R")
      (footprint "eagle-import:R0201")
      (fields (field (name "PARTNO") "RC0201FR-0733RL"))
      (libsource (lib "eagle-import") (part "R-US_R0201"))
    )
    (comp (ref "R55")
      (value "33R")
      (footprint "eagle-import:R0201")
      (fields (field (name "PARTNO") "RC0201FR-0733RL"))
      (libsource (lib "eagle-import") (part "R-US_R0201"))
    )
    (comp (ref "R56")
      (value "33R")
      (footprint "eagle-import:R0201")
      (fields (field (name "PARTNO") "RC0201FR-0733RL"))
      (libsource (lib "eagle-import") (part "R-US_R0201"))
    )
    (comp (ref "R57")
      (value "33R")
      (footprint "eagle-import:R0201")
      (fields (field (name "PARTNO") "RC0201FR-0733RL"))
      (libsource (lib "eagle-import") (part "R-US_R0201"))
    )
    (comp (ref "R58")
      (value "33R")
      (footprint "eagle-import:R0201")
      (fields (field (name "PARTNO") "RC0201FR-0733RL"))
      (libsource (lib "eagle-import") (part "R-US_R0201"))
    )
    (comp (ref "R59")
      (value "33R")
      (footprint "eagle-import:R0201")
      (fields (field (name "PARTNO") "RC0201FR-0733RL"))
      (libsource (lib "eagle-import") (part "R-US_R0201"))
    )
    (comp (ref "R60")
      (value "33R")
      (footprint "eagle-import:R0201")
      (fields (field (name "PARTNO") "RC0201FR-0733RL"))
      (libsource (lib "eagle-import") (part "R-US_R0201"))
    )
    (comp (ref "R61")
      (value "33R")
      (footprint "eagle-import:R0201")
      (fields (field (name "PARTNO") "RC0201FR-0733RL"))
      (libsource (lib "eagle-import") (part "R-US_R0201"))
    )
    (comp (ref "R62")
      (value "0R")
      (footprint "eagle-import:R0603")
      (fields (field (name "PARTNO") "RCS06030000Z0EA"))
      (libsource (lib "eagle-import") (part "resistor_R-US_R0603"))
    )
    (comp (ref "R63")
      (value "33R")
      (footprint "eagle-import:R0201")
      (fields (field (name "PARTNO") "RC0201FR-0733RL"))
      (libsource (lib "eagle-import") (part "R-US_R0201"))
    )
    (comp (ref "R64")
      (value "33R")
      (footprint "eagle-import:R0201")
      (fields (field (name "PARTNO") "RC0201FR-0733RL"))
      (libsource (lib "eagle-import") (part "R-US_R0201"))
    )
    (comp (ref "R65")
      (value "33R")
      (footprint "eagle-import:R0201")
      (fields (field (name "PARTNO") "RC0201FR-0733RL"))
      (libsource (lib "eagle-import") (part "R-US_R0201"))
    )
    (comp (ref "R66")
      (value "33R")
      (footprint "eagle-import:R0201")
      (fields (field (name "PARTNO") "RC0201FR-0733RL"))
      (libsource (lib "eagle-import") (part "R-US_R0201"))
    )
    (comp (ref "R67")
      (value "33R")
      (footprint "eagle-import:R0201")
      (fields (field (name "PARTNO") "RC0201FR-0733RL"))
      (libsource (lib "eagle-import") (part "R-US_R0201"))
    )
    (comp (ref "R68")
      (value "33R")
      (footprint "eagle-import:R0201")
      (fields (field (name "PARTNO") "RC0201FR-0733RL"))
      (libsource (lib "eagle-import") (part "R-US_R0201"))
    )
    (comp (ref "R69")
      (value "33R")
      (footprint "eagle-import:R0201")
      (fields (field (name "PARTNO") "RC0201FR-0733RL"))
      (libsource (lib "eagle-import") (part "R-US_R0201"))
    )
    (comp (ref "R70")
      (value "33R")
      (footprint "eagle-import:R0201")
      (fields (field (name "PARTNO") "RC0201FR-0733RL"))
      (libsource (lib "eagle-import") (part "R-US_R0201"))
    )
    (comp (ref "R71")
      (value "33R")
      (footprint "eagle-import:R0201")
      (fields (field (name "PARTNO") "RC0201FR-0733RL"))
      (libsource (lib "eagle-import") (part "R-US_R0201"))
    )
    (comp (ref "R72")
      (value "33R")
      (footprint "eagle-import:R0201")
      (fields (field (name "PARTNO") "RC0201FR-0733RL"))
      (libsource (lib "eagle-import") (part "R-US_R0201"))
    )
    (comp (ref "R73")
      (value "33R")
      (footprint "eagle-import:R0201")
      (fields (field (name "PARTNO") "RC0201FR-0733RL"))
      (libsource (lib "eagle-import") (part "R-US_R0201"))
    )
    (comp (ref "R74")
      (value "33R")
      (footprint "eagle-import:R0201")
      (fields (field (name "PARTNO") "RC0201FR-0733RL"))
      (libsource (lib "eagle-import") (part "R-US_R0201"))
    )
    (comp (ref "R75")
      (value "33R")
      (footprint "eagle-import:R0201")
      (fields (field (name "PARTNO") "RC0201FR-0733RL"))
      (libsource (lib "eagle-import") (part "R-US_R0201"))
    )
    (comp (ref "R76")
      (value "33R")
      (footprint "eagle-import:R0201")
      (fields (field (name "PARTNO") "RC0201FR-0733RL"))
      (libsource (lib "eagle-import") (part "R-US_R0201"))
    )
    (comp (ref "R77")
      (value "33R")
      (footprint "eagle-import:R0201")
      (fields (field (name "PARTNO") "RC0201FR-0733RL"))
      (libsource (lib "eagle-import") (part "R-US_R0201"))
    )
    (comp (ref "R78")
      (value "33R")
      (footprint "eagle-import:R0201")
      (fields (field (name "PARTNO") "RC0201FR-0733RL"))
      (libsource (lib "eagle-import") (part "R-US_R0201"))
    )
    (comp (ref "R79")
      (value "560R")
      (footprint "eagle-import:R0603")
      (fields (field (name "PARTNO") "ESR03EZPF5600"))
      (libsource (lib "eagle-import") (part "resistor_R-US_R0603"))
    )
    (comp (ref "X1")
      (value "1050270001_SD_CARD_CONNECTOR")
      (footprint "eagle-import:1050270001")
      (fields (field (name "PARTNO") "1050270001"))
      (libsource (lib "eagle-import") (part "1050270001_SD_CARD_CONNECTOR"))
    )
    (comp (ref "X2")
      (value "3221-10-0300-00")
      (footprint "eagle-import:3221-10-0300-00")
      (libsource (lib "eagle-import") (part "3221-10-0300-00"))
    )
  )
  (nets
    (net (code "1") (name "+3V3") (class "Default")
      (node (ref "3V3D") (pin "1") (pinfunction "1_1") (pintype "passive"))
      (node (ref "C12") (pin "1") (pinfunction "1_1") (pintype "passive"))
      (node (ref "C13") (pin "1") (pinfunction "1_1") (pintype "passive"))
      (node (ref "C14") (pin "1") (pinfunction "1_1") (pintype "passive"))
      (node (ref "C15") (pin "1") (pinfunction "1_1") (pintype "passive"))
      (node (ref "C16") (pin "1") (pinfunction "1_1") (pintype "passive"))
      (node (ref "C20") (pin "1") (pinfunction "1_1") (pintype "passive"))
      (node (ref "C32") (pin "1") (pinfunction "1_1") (pintype "passive"))
      (node (ref "C36") (pin "+") (pinfunction "+_+") (pintype "passive"))
      (node (ref "C42") (pin "1") (pinfunction "1_1") (pintype "passive"))
      (node (ref "C43") (pin "1") (pinfunction "1_1") (pintype "passive"))
      (node (ref "C44") (pin "+") (pinfunction "+_+") (pintype "passive"))
      (node (ref "C47") (pin "1") (pinfunction "1_1") (pintype "passive"))
      (node (ref "C48") (pin "1") (pinfunction "1_1") (pintype "passive"))
      (node (ref "C49") (pin "1") (pinfunction "1_1") (pintype "passive"))
      (node (ref "C55") (pin "1") (pinfunction "1_1") (pintype "passive"))
      (node (ref "C56") (pin "1") (pinfunction "1_1") (pintype "passive"))
      (node (ref "C57") (pin "1") (pinfunction "1_1") (pintype "passive"))
      (node (ref "C58") (pin "1") (pinfunction "1_1") (pintype "passive"))
      (node (ref "C59") (pin "1") (pinfunction "1_1") (pintype "passive"))
      (node (ref "C60") (pin "1") (pinfunction "1_1") (pintype "passive"))
      (node (ref "C63") (pin "1") (pinfunction "1_1") (pintype "passive"))
      (node (ref "C66") (pin "1") (pinfunction "1_1") (pintype "passive"))
      (node (ref "C67") (pin "1") (pinfunction "1_1") (pintype "passive"))
      (node (ref "C68") (pin "1") (pinfunction "1_1") (pintype "passive"))
      (node (ref "C69") (pin "1") (pinfunction "1_1") (pintype "passive"))
      (node (ref "C7") (pin "1") (pinfunction "1_1") (pintype "passive"))
      (node (ref "C76") (pin "1") (pinfunction "1_1") (pintype "passive"))
      (node (ref "C77") (pin "1") (pinfunction "1_1") (pintype "passive"))
      (node (ref "C78") (pin "1") (pinfunction "1_1") (pintype "passive"))
      (node (ref "C79") (pin "1") (pinfunction "1_1") (pintype "passive"))
      (node (ref "C80") (pin "1") (pinfunction "1_1") (pintype "passive"))
      (node (ref "IC2") (pin "1") (pinfunction "VDD_1") (pintype "power_in"))
      (node (ref "IC2") (pin "14") (pinfunction "VDD_14") (pintype "power_in"))
      (node (ref "IC2") (pin "27") (pinfunction "VDD_27") (pintype "power_in"))
      (node (ref "IC2") (pin "3") (pinfunction "VDDQ_3") (pintype "power_in"))
      (node (ref "IC2") (pin "43") (pinfunction "VDDQ_43") (pintype "power_in"))
      (node (ref "IC2") (pin "49") (pinfunction "VDDQ_49") (pintype "power_in"))
      (node (ref "IC2") (pin "9") (pinfunction "VDDQ_9") (pintype "power_in"))
      (node (ref "IC3") (pin "108") (pinfunction "VDD_108") (pintype "power_in"))
      (node (ref "IC3") (pin "121") (pinfunction "VDD_121") (pintype "power_in"))
      (node (ref "IC3") (pin "131") (pinfunction "VDD_131") (pintype "power_in"))
      (node (ref "IC3") (pin "143") (pinfunction "PDR_ON_143") (pintype "input"))
      (node (ref "IC3") (pin "144") (pinfunction "VDD_144") (pintype "power_in"))
      (node (ref "IC3") (pin "17") (pinfunction "VDD_17") (pintype "power_in"))
      (node (ref "IC3") (pin "30") (pinfunction "VDD_30") (pintype "power_in"))
      (node (ref "IC3") (pin "39") (pinfunction "VDD_39") (pintype "power_in"))
      (node (ref "IC3") (pin "52") (pinfunction "VDD_52") (pintype "power_in"))
      (node (ref "IC3") (pin "6") (pinfunction "VBAT_6") (pintype "power_in"))
      (node (ref "IC3") (pin "62") (pinfunction "VDD_62") (pintype "power_in"))
      (node (ref "IC3") (pin "72") (pinfunction "VDD_72") (pintype "power_in"))
      (node (ref "IC3") (pin "84") (pinfunction "VDD_84") (pintype "power_in"))
      (node (ref "IC3") (pin "95") (pinfunction "VDD33USB_95") (pintype "power_in"))
      (node (ref "IC4") (pin "2") (pinfunction "VOUT_2") (pintype "bidirectional"))
      (node (ref "IC4") (pin "PAD") (pinfunction "PAD_PAD") (pintype "bidirectional"))
      (node (ref "IC5") (pin "10") (pinfunction "VL_10") (pintype "bidirectional"))
      (node (ref "IC5") (pin "9") (pinfunction "VD_9") (pintype "bidirectional"))
      (node (ref "JP3") (pin "1") (pinfunction "1_1") (pintype "passive"))
      (node (ref "R10") (pin "1") (pinfunction "1_1") (pintype "passive"))
      (node (ref "R11") (pin "1") (pinfunction "1_1") (pintype "passive"))
      (node (ref "R6") (pin "1") (pinfunction "1_1") (pintype "passive"))
      (node (ref "X1") (pin "P4") (pinfunction "VDD_P4") (pintype "bidirectional"))
      (node (ref "X2") (pin "1") (pinfunction "1_1") (pintype "bidirectional"))
    )
    (net (code "2") (name "+5V") (class "Default")
      (node (ref "5V") (pin "1") (pinfunction "1_1") (pintype "passive"))
      (node (ref "C61") (pin "1") (pinfunction "1_1") (pintype "passive"))
      (node (ref "C62") (pin "+") (pinfunction "+_+") (pintype "passive"))
      (node (ref "IC4") (pin "3") (pinfunction "VIN_3") (pintype "bidirectional"))
      (node (ref "IC7") (pin "1") (pinfunction "VIN_1") (pintype "bidirectional"))
      (node (ref "IC7") (pin "3") (pinfunction "EN_3") (pintype "bidirectional"))
      (node (ref "IC9") (pin "4") (pinfunction "EN_4") (pintype "bidirectional"))
      (node (ref "IC9") (pin "6") (pinfunction "IN_6") (pintype "bidirectional"))
      (node (ref "JP3") (pin "20") (pinfunction "20_20") (pintype "passive"))
      (node (ref "L1") (pin "P$1") (pinfunction "P$1_P$1") (pintype "bidirectional"))
    )
    (net (code "3") (name "/A0") (class "Default")
      (node (ref "IC3") (pin "10") (pinfunction "PF0_10") (pintype "bidirectional"))
      (node (ref "R36") (pin "1") (pinfunction "1_1") (pintype "passive"))
    )
    (net (code "4") (name "/A1") (class "Default")
      (node (ref "IC3") (pin "11") (pinfunction "PF1_11") (pintype "bidirectional"))
      (node (ref "R40") (pin "1") (pinfunction "1_1") (pintype "passive"))
    )
    (net (code "5") (name "/A2") (class "Default")
      (node (ref "IC3") (pin "12") (pinfunction "PF2_12") (pintype "bidirectional"))
      (node (ref "R42") (pin "1") (pinfunction "1_1") (pintype "passive"))
    )
    (net (code "6") (name "/A3") (class "Default")
      (node (ref "IC3") (pin "13") (pinfunction "PF3_13") (pintype "bidirectional"))
      (node (ref "R41") (pin "1") (pinfunction "1_1") (pintype "passive"))
    )
    (net (code "7") (name "/A4") (class "Default")
      (node (ref "IC3") (pin "14") (pinfunction "PF4_14") (pintype "bidirectional"))
      (node (ref "R43") (pin "1") (pinfunction "1_1") (pintype "passive"))
    )
    (net (code "8") (name "/A5") (class "Default")
      (node (ref "IC3") (pin "15") (pinfunction "PF5_15") (pintype "bidirectional"))
      (node (ref "R44") (pin "1") (pinfunction "1_1") (pintype "passive"))
    )
    (net (code "9") (name "/A6") (class "Default")
      (node (ref "IC3") (pin "50") (pinfunction "PF12_50") (pintype "bidirectional"))
      (node (ref "R45") (pin "1") (pinfunction "1_1") (pintype "passive"))
    )
    (net (code "10") (name "/A7") (class "Default")
      (node (ref "IC3") (pin "53") (pinfunction "PF13_53") (pintype "bidirectional"))
      (node (ref "R46") (pin "1") (pinfunction "1_1") (pintype "passive"))
    )
    (net (code "11") (name "/A8") (class "Default")
      (node (ref "IC3") (pin "54") (pinfunction "PF14_54") (pintype "bidirectional"))
      (node (ref "R47") (pin "1") (pinfunction "1_1") (pintype "passive"))
    )
    (net (code "12") (name "/A9") (class "Default")
      (node (ref "IC3") (pin "55") (pinfunction "PF15_55") (pintype "bidirectional"))
      (node (ref "R48") (pin "1") (pinfunction "1_1") (pintype "passive"))
    )
    (net (code "13") (name "/A10") (class "Default")
      (node (ref "IC3") (pin "56") (pinfunction "PG0_56") (pintype "bidirectional"))
      (node (ref "R49") (pin "1") (pinfunction "1_1") (pintype "passive"))
    )
    (net (code "14") (name "/A11") (class "Default")
      (node (ref "IC3") (pin "57") (pinfunction "PG1_57") (pintype "bidirectional"))
      (node (ref "R50") (pin "1") (pinfunction "1_1") (pintype "passive"))
    )
    (net (code "15") (name "/A12") (class "Default")
      (node (ref "IC3") (pin "87") (pinfunction "PG2_87") (pintype "bidirectional"))
      (node (ref "R51") (pin "1") (pinfunction "1_1") (pintype "passive"))
    )
    (net (code "16") (name "/AQ0") (class "Default")
      (node (ref "IC2") (pin "23") (pinfunction "A0_23") (pintype "input"))
      (node (ref "R36") (pin "2") (pinfunction "2_2") (pintype "passive"))
    )
    (net (code "17") (name "/AQ1") (class "Default")
      (node (ref "IC2") (pin "24") (pinfunction "A1_24") (pintype "input"))
      (node (ref "R40") (pin "2") (pinfunction "2_2") (pintype "passive"))
    )
    (net (code "18") (name "/AQ2") (class "Default")
      (node (ref "IC2") (pin "25") (pinfunction "A2_25") (pintype "input"))
      (node (ref "R42") (pin "2") (pinfunction "2_2") (pintype "passive"))
    )
    (net (code "19") (name "/AQ3") (class "Default")
      (node (ref "IC2") (pin "26") (pinfunction "A3_26") (pintype "input"))
      (node (ref "R41") (pin "2") (pinfunction "2_2") (pintype "passive"))
    )
    (net (code "20") (name "/AQ4") (class "Default")
      (node (ref "IC2") (pin "29") (pinfunction "A4_29") (pintype "input"))
      (node (ref "R43") (pin "2") (pinfunction "2_2") (pintype "passive"))
    )
    (net (code "21") (name "/AQ5") (class "Default")
      (node (ref "IC2") (pin "30") (pinfunction "A5_30") (pintype "input"))
      (node (ref "R44") (pin "2") (pinfunction "2_2") (pintype "passive"))
    )
    (net (code "22") (name "/AQ6") (class "Default")
      (node (ref "IC2") (pin "31") (pinfunction "A6_31") (pintype "input"))
      (node (ref "R45") (pin "2") (pinfunction "2_2") (pintype "passive"))
    )
    (net (code "23") (name "/AQ7") (class "Default")
      (node (ref "IC2") (pin "32") (pinfunction "A7_32") (pintype "input"))
      (node (ref "R46") (pin "2") (pinfunction "2_2") (pintype "passive"))
    )
    (net (code "24") (name "/AQ8") (class "Default")
      (node (ref "IC2") (pin "33") (pinfunction "A8_33") (pintype "input"))
      (node (ref "R47") (pin "2") (pinfunction "2_2") (pintype "passive"))
    )
    (net (code "25") (name "/AQ9") (class "Default")
      (node (ref "IC2") (pin "34") (pinfunction "A9_34") (pintype "input"))
      (node (ref "R48") (pin "2") (pinfunction "2_2") (pintype "passive"))
    )
    (net (code "26") (name "/AQ10") (class "Default")
      (node (ref "IC2") (pin "22") (pinfunction "A10/AP_22") (pintype "input"))
      (node (ref "R49") (pin "2") (pinfunction "2_2") (pintype "passive"))
    )
    (net (code "27") (name "/AQ11") (class "Default")
      (node (ref "IC2") (pin "35") (pinfunction "A11_35") (pintype "input"))
      (node (ref "R50") (pin "2") (pinfunction "2_2") (pintype "passive"))
    )
    (net (code "28") (name "/AQ12") (class "Default")
      (node (ref "IC2") (pin "36") (pinfunction "A12_36") (pintype "input"))
      (node (ref "R51") (pin "2") (pinfunction "2_2") (pintype "passive"))
    )
    (net (code "29") (name "/BA0-R") (class "Default")
      (node (ref "IC2") (pin "20") (pinfunction "BA0_20") (pintype "input"))
      (node (ref "R60") (pin "2") (pinfunction "2_2") (pintype "passive"))
    )
    (net (code "30") (name "/BA0-S") (class "Default")
      (node (ref "IC3") (pin "89") (pinfunction "PG4_89") (pintype "bidirectional"))
      (node (ref "R60") (pin "1") (pinfunction "1_1") (pintype "passive"))
    )
    (net (code "31") (name "/BA1-R") (class "Default")
      (node (ref "IC2") (pin "21") (pinfunction "BA1_21") (pintype "input"))
      (node (ref "R61") (pin "2") (pinfunction "2_2") (pintype "passive"))
    )
    (net (code "32") (name "/BA1-S") (class "Default")
      (node (ref "IC3") (pin "90") (pinfunction "PG5_90") (pintype "bidirectional"))
      (node (ref "R61") (pin "1") (pinfunction "1_1") (pintype "passive"))
    )
    (net (code "33") (name "/CAS-R") (class "Default")
      (node (ref "IC2") (pin "17") (pinfunction "CAS#_17") (pintype "input"))
      (node (ref "R57") (pin "2") (pinfunction "2_2") (pintype "passive"))
    )
    (net (code "34") (name "/CAS-S") (class "Default")
      (node (ref "IC3") (pin "132") (pinfunction "PG15_132") (pintype "bidirectional"))
      (node (ref "R57") (pin "1") (pinfunction "1_1") (pintype "passive"))
    )
    (net (code "35") (name "/CKE-R") (class "Default")
      (node (ref "IC2") (pin "37") (pinfunction "CKE_37") (pintype "input"))
      (node (ref "R52") (pin "2") (pinfunction "2_2") (pintype "passive"))
    )
    (net (code "36") (name "/CKE-S") (class "Default")
      (node (ref "IC3") (pin "29") (pinfunction "PC3_C_29") (pintype "bidirectional"))
      (node (ref "R52") (pin "1") (pinfunction "1_1") (pintype "passive"))
    )
    (net (code "37") (name "/CLK-R") (class "Default")
      (node (ref "IC2") (pin "38") (pinfunction "CLK_38") (pintype "input"))
      (node (ref "R53") (pin "2") (pinfunction "2_2") (pintype "passive"))
    )
    (net (code "38") (name "/CLK-S") (class "Default")
      (node (ref "IC3") (pin "93") (pinfunction "PG8_93") (pintype "bidirectional"))
      (node (ref "R53") (pin "1") (pinfunction "1_1") (pintype "passive"))
    )
    (net (code "39") (name "/CS-R") (class "Default")
      (node (ref "IC2") (pin "19") (pinfunction "CS#_19") (pintype "input"))
      (node (ref "R59") (pin "2") (pinfunction "2_2") (pintype "passive"))
    )
    (net (code "40") (name "/CS-S") (class "Default")
      (node (ref "IC3") (pin "28") (pinfunction "PC2_C_28") (pintype "bidirectional"))
      (node (ref "R59") (pin "1") (pinfunction "1_1") (pintype "passive"))
    )
    (net (code "41") (name "/D0") (class "Default")
      (node (ref "IC3") (pin "85") (pinfunction "PD14_85") (pintype "bidirectional"))
      (node (ref "R63") (pin "1") (pinfunction "1_1") (pintype "passive"))
    )
    (net (code "42") (name "/D1") (class "Default")
      (node (ref "IC3") (pin "86") (pinfunction "PD15_86") (pintype "bidirectional"))
      (node (ref "R64") (pin "1") (pinfunction "1_1") (pintype "passive"))
    )
    (net (code "43") (name "/D2") (class "Default")
      (node (ref "IC3") (pin "114") (pinfunction "PD0_114") (pintype "bidirectional"))
      (node (ref "R65") (pin "1") (pinfunction "1_1") (pintype "passive"))
    )
    (net (code "44") (name "/D3") (class "Default")
      (node (ref "IC3") (pin "115") (pinfunction "PD1_115") (pintype "bidirectional"))
      (node (ref "R66") (pin "1") (pinfunction "1_1") (pintype "passive"))
    )
    (net (code "45") (name "/D4") (class "Default")
      (node (ref "IC3") (pin "58") (pinfunction "PE7_58") (pintype "bidirectional"))
      (node (ref "R67") (pin "1") (pinfunction "1_1") (pintype "passive"))
    )
    (net (code "46") (name "/D5") (class "Default")
      (node (ref "IC3") (pin "59") (pinfunction "PE8_59") (pintype "bidirectional"))
      (node (ref "R68") (pin "1") (pinfunction "1_1") (pintype "passive"))
    )
    (net (code "47") (name "/D6") (class "Default")
      (node (ref "IC3") (pin "60") (pinfunction "PE9_60") (pintype "bidirectional"))
      (node (ref "R69") (pin "1") (pinfunction "1_1") (pintype "passive"))
    )
    (net (code "48") (name "/D7") (class "Default")
      (node (ref "IC3") (pin "63") (pinfunction "PE10_63") (pintype "bidirectional"))
      (node (ref "R70") (pin "1") (pinfunction "1_1") (pintype "passive"))
    )
    (net (code "49") (name "/D8") (class "Default")
      (node (ref "IC3") (pin "64") (pinfunction "PE11_64") (pintype "bidirectional"))
      (node (ref "R71") (pin "1") (pinfunction "1_1") (pintype "passive"))
    )
    (net (code "50") (name "/D9") (class "Default")
      (node (ref "IC3") (pin "65") (pinfunction "PE12_65") (pintype "bidirectional"))
      (node (ref "R72") (pin "1") (pinfunction "1_1") (pintype "passive"))
    )
    (net (code "51") (name "/D10") (class "Default")
      (node (ref "IC3") (pin "66") (pinfunction "PE13_66") (pintype "bidirectional"))
      (node (ref "R73") (pin "1") (pinfunction "1_1") (pintype "passive"))
    )
    (net (code "52") (name "/D11") (class "Default")
      (node (ref "IC3") (pin "67") (pinfunction "PE14_67") (pintype "bidirectional"))
      (node (ref "R74") (pin "1") (pinfunction "1_1") (pintype "passive"))
    )
    (net (code "53") (name "/D12") (class "Default")
      (node (ref "IC3") (pin "68") (pinfunction "PE15_68") (pintype "bidirectional"))
      (node (ref "R75") (pin "1") (pinfunction "1_1") (pintype "passive"))
    )
    (net (code "54") (name "/D13") (class "Default")
      (node (ref "IC3") (pin "77") (pinfunction "PD8_77") (pintype "bidirectional"))
      (node (ref "R76") (pin "1") (pinfunction "1_1") (pintype "passive"))
    )
    (net (code "55") (name "/D14") (class "Default")
      (node (ref "IC3") (pin "78") (pinfunction "PD9_78") (pintype "bidirectional"))
      (node (ref "R77") (pin "1") (pinfunction "1_1") (pintype "passive"))
    )
    (net (code "56") (name "/D15") (class "Default")
      (node (ref "IC3") (pin "79") (pinfunction "PD10_79") (pintype "bidirectional"))
      (node (ref "R78") (pin "1") (pinfunction "1_1") (pintype "passive"))
    )
    (net (code "57") (name "/DQ0") (class "Default")
      (node (ref "IC2") (pin "2") (pinfunction "DQ0_2") (pintype "bidirectional"))
      (node (ref "R63") (pin "2") (pinfunction "2_2") (pintype "passive"))
    )
    (net (code "58") (name "/DQ1") (class "Default")
      (node (ref "IC2") (pin "4") (pinfunction "DQ1_4") (pintype "bidirectional"))
      (node (ref "R64") (pin "2") (pinfunction "2_2") (pintype "passive"))
    )
    (net (code "59") (name "/DQ2") (class "Default")
      (node (ref "IC2") (pin "5") (pinfunction "DQ2_5") (pintype "bidirectional"))
      (node (ref "R65") (pin "2") (pinfunction "2_2") (pintype "passive"))
    )
    (net (code "60") (name "/DQ3") (class "Default")
      (node (ref "IC2") (pin "7") (pinfunction "DQ3_7") (pintype "bidirectional"))
      (node (ref "R66") (pin "2") (pinfunction "2_2") (pintype "passive"))
    )
    (net (code "61") (name "/DQ4") (class "Default")
      (node (ref "IC2") (pin "8") (pinfunction "DQ4_8") (pintype "bidirectional"))
      (node (ref "R67") (pin "2") (pinfunction "2_2") (pintype "passive"))
    )
    (net (code "62") (name "/DQ5") (class "Default")
      (node (ref "IC2") (pin "10") (pinfunction "DQ5_10") (pintype "bidirectional"))
      (node (ref "R68") (pin "2") (pinfunction "2_2") (pintype "passive"))
    )
    (net (code "63") (name "/DQ6") (class "Default")
      (node (ref "IC2") (pin "11") (pinfunction "DQ6_11") (pintype "bidirectional"))
      (node (ref "R69") (pin "2") (pinfunction "2_2") (pintype "passive"))
    )
    (net (code "64") (name "/DQ7") (class "Default")
      (node (ref "IC2") (pin "13") (pinfunction "DQ7_13") (pintype "bidirectional"))
      (node (ref "R70") (pin "2") (pinfunction "2_2") (pintype "passive"))
    )
    (net (code "65") (name "/DQ8") (class "Default")
      (node (ref "IC2") (pin "42") (pinfunction "DQ8_42") (pintype "bidirectional"))
      (node (ref "R71") (pin "2") (pinfunction "2_2") (pintype "passive"))
    )
    (net (code "66") (name "/DQ9") (class "Default")
      (node (ref "IC2") (pin "44") (pinfunction "DQ9_44") (pintype "bidirectional"))
      (node (ref "R72") (pin "2") (pinfunction "2_2") (pintype "passive"))
    )
    (net (code "67") (name "/DQ10") (class "Default")
      (node (ref "IC2") (pin "45") (pinfunction "DQ10_45") (pintype "bidirectional"))
      (node (ref "R73") (pin "2") (pinfunction "2_2") (pintype "passive"))
    )
    (net (code "68") (name "/DQ11") (class "Default")
      (node (ref "IC2") (pin "47") (pinfunction "DQ11_47") (pintype "bidirectional"))
      (node (ref "R74") (pin "2") (pinfunction "2_2") (pintype "passive"))
    )
    (net (code "69") (name "/DQ12") (class "Default")
      (node (ref "IC2") (pin "48") (pinfunction "DQ12_48") (pintype "bidirectional"))
      (node (ref "R75") (pin "2") (pinfunction "2_2") (pintype "passive"))
    )
    (net (code "70") (name "/DQ13") (class "Default")
      (node (ref "IC2") (pin "50") (pinfunction "DQ13_50") (pintype "bidirectional"))
      (node (ref "R76") (pin "2") (pinfunction "2_2") (pintype "passive"))
    )
    (net (code "71") (name "/DQ14") (class "Default")
      (node (ref "IC2") (pin "51") (pinfunction "DQ14_51") (pintype "bidirectional"))
      (node (ref "R77") (pin "2") (pinfunction "2_2") (pintype "passive"))
    )
    (net (code "72") (name "/DQ15") (class "Default")
      (node (ref "IC2") (pin "53") (pinfunction "DQ15_53") (pintype "bidirectional"))
      (node (ref "R78") (pin "2") (pinfunction "2_2") (pintype "passive"))
    )
    (net (code "73") (name "/I2C2_SCL") (class "Default")
      (node (ref "IC3") (pin "69") (pinfunction "PB10_69") (pintype "bidirectional"))
      (node (ref "IC5") (pin "11") (pinfunction "SCL/CCLK_11") (pintype "bidirectional"))
      (node (ref "JP1") (pin "2") (pinfunction "2_2") (pintype "passive"))
      (node (ref "R10") (pin "2") (pinfunction "2_2") (pintype "passive"))
    )
    (net (code "74") (name "/I2C2_SDA") (class "Default")
      (node (ref "IC3") (pin "70") (pinfunction "PB11_70") (pintype "bidirectional"))
      (node (ref "IC5") (pin "12") (pinfunction "SDA/CDIN_12") (pintype "bidirectional"))
      (node (ref "JP1") (pin "1") (pinfunction "1_1") (pintype "passive"))
      (node (ref "R11") (pin "2") (pinfunction "2_2") (pintype "passive"))
    )
    (net (code "75") (name "/LD-R") (class "Default")
      (node (ref "IC2") (pin "15") (pinfunction "LDQM_15") (pintype "input"))
      (node (ref "R55") (pin "2") (pinfunction "2_2") (pintype "passive"))
    )
    (net (code "76") (name "/LD-S") (class "Default")
      (node (ref "IC3") (pin "141") (pinfunction "PE0_141") (pintype "bidirectional"))
      (node (ref "R55") (pin "1") (pinfunction "1_1") (pintype "passive"))
    )
    (net (code "77") (name "/PA0") (class "Default")
      (node (ref "IC3") (pin "34") (pinfunction "PA0_34") (pintype "bidirectional"))
      (node (ref "JP1") (pin "17") (pinfunction "17_17") (pintype "passive"))
    )
    (net (code "78") (name "/PA1") (class "Default")
      (node (ref "IC3") (pin "35") (pinfunction "PA1_35") (pintype "bidirectional"))
      (node (ref "JP1") (pin "18") (pinfunction "18_18") (pintype "passive"))
    )
    (net (code "79") (name "/PA2") (class "Default")
      (node (ref "IC3") (pin "36") (pinfunction "PA2_36") (pintype "bidirectional"))
      (node (ref "JP1") (pin "15") (pinfunction "15_15") (pintype "passive"))
    )
    (net (code "80") (name "/PA3") (class "Default")
      (node (ref "IC3") (pin "37") (pinfunction "PA3_37") (pintype "bidirectional"))
      (node (ref "JP1") (pin "16") (pinfunction "16_16") (pintype "passive"))
    )
    (net (code "81") (name "/PA4") (class "Default")
      (node (ref "IC3") (pin "40") (pinfunction "PA4_40") (pintype "bidirectional"))
      (node (ref "JP1") (pin "13") (pinfunction "13_13") (pintype "passive"))
    )
    (net (code "82") (name "/PA5") (class "Default")
      (node (ref "IC3") (pin "41") (pinfunction "PA5_41") (pintype "bidirectional"))
      (node (ref "JP1") (pin "14") (pinfunction "14_14") (pintype "passive"))
    )
    (net (code "83") (name "/PA6") (class "Default")
      (node (ref "IC3") (pin "42") (pinfunction "PA6_42") (pintype "bidirectional"))
      (node (ref "JP1") (pin "11") (pinfunction "11_11") (pintype "passive"))
    )
    (net (code "84") (name "/PA7") (class "Default")
      (node (ref "IC3") (pin "43") (pinfunction "PA7_43") (pintype "bidirectional"))
      (node (ref "JP1") (pin "12") (pinfunction "12_12") (pintype "passive"))
    )
    (net (code "85") (name "/PA8") (class "Default")
      (node (ref "IC3") (pin "100") (pinfunction "PA8_100") (pintype "bidirectional"))
      (node (ref "JP3") (pin "13") (pinfunction "13_13") (pintype "passive"))
    )
    (net (code "86") (name "/PA9") (class "Default")
      (node (ref "IC3") (pin "101") (pinfunction "PA9_101") (pintype "bidirectional"))
      (node (ref "JP3") (pin "16") (pinfunction "16_16") (pintype "passive"))
    )
    (net (code "87") (name "/PA10") (class "Default")
      (node (ref "IC3") (pin "102") (pinfunction "PA10_102") (pintype "bidirectional"))
      (node (ref "JP3") (pin "15") (pinfunction "15_15") (pintype "passive"))
    )
    (net (code "88") (name "/PA11") (class "Default")
      (node (ref "IC3") (pin "103") (pinfunction "PA11_103") (pintype "bidirectional"))
      (node (ref "JP3") (pin "18") (pinfunction "18_18") (pintype "passive"))
    )
    (net (code "89") (name "/PA12") (class "Default")
      (node (ref "IC3") (pin "104") (pinfunction "PA12_104") (pintype "bidirectional"))
      (node (ref "JP3") (pin "17") (pinfunction "17_17") (pintype "passive"))
    )
    (net (code "90") (name "/PB0") (class "Default")
      (node (ref "IC3") (pin "46") (pinfunction "PB0_46") (pintype "bidirectional"))
      (node (ref "JP1") (pin "7") (pinfunction "7_7") (pintype "passive"))
    )
    (net (code "91") (name "/PB1") (class "Default")
      (node (ref "IC3") (pin "47") (pinfunction "PB1_47") (pintype "bidirectional"))
      (node (ref "JP1") (pin "8") (pinfunction "8_8") (pintype "passive"))
    )
    (net (code "92") (name "/PB5") (class "Default")
      (node (ref "IC3") (pin "135") (pinfunction "PB5_135") (pintype "bidirectional"))
      (node (ref "JP1") (pin "29") (pinfunction "29_29") (pintype "passive"))
    )
    (net (code "93") (name "/PB6") (class "Default")
      (node (ref "IC3") (pin "136") (pinfunction "PB6_136") (pintype "bidirectional"))
      (node (ref "JP1") (pin "30") (pinfunction "30_30") (pintype "passive"))
    )
    (net (code "94") (name "/PB7") (class "Default")
      (node (ref "IC3") (pin "137") (pinfunction "PB7_137") (pintype "bidirectional"))
      (node (ref "JP1") (pin "27") (pinfunction "27_27") (pintype "passive"))
    )
    (net (code "95") (name "/PB8") (class "Default")
      (node (ref "IC3") (pin "139") (pinfunction "PB8_139") (pintype "bidirectional"))
      (node (ref "JP1") (pin "28") (pinfunction "28_28") (pintype "passive"))
    )
    (net (code "96") (name "/PB9") (class "Default")
      (node (ref "IC3") (pin "140") (pinfunction "PB9_140") (pintype "bidirectional"))
    )
    (net (code "97") (name "/PB12") (class "Default")
      (node (ref "IC3") (pin "73") (pinfunction "PB12_73") (pintype "bidirectional"))
      (node (ref "JP3") (pin "4") (pinfunction "4_4") (pintype "passive"))
    )
    (net (code "98") (name "/PB13") (class "Default")
      (node (ref "JP3") (pin "3") (pinfunction "3_3") (pintype "passive"))
      (node (ref "R14") (pin "1") (pinfunction "1_1") (pintype "passive"))
    )
    (net (code "99") (name "/PB14") (class "Default")
      (node (ref "IC3") (pin "75") (pinfunction "PB14_75") (pintype "bidirectional"))
      (node (ref "JP3") (pin "6") (pinfunction "6_6") (pintype "passive"))
    )
    (net (code "100") (name "/PB15") (class "Default")
      (node (ref "JP3") (pin "5") (pinfunction "5_5") (pintype "passive"))
      (node (ref "R15") (pin "1") (pinfunction "1_1") (pintype "passive"))
    )
    (net (code "101") (name "/PC1") (class "Default")
      (node (ref "IC3") (pin "27") (pinfunction "PC1_27") (pintype "bidirectional"))
      (node (ref "JP1") (pin "26") (pinfunction "26_26") (pintype "passive"))
    )
    (net (code "102") (name "/PC4") (class "Default")
      (node (ref "IC3") (pin "44") (pinfunction "PC4_44") (pintype "bidirectional"))
      (node (ref "JP1") (pin "9") (pinfunction "9_9") (pintype "passive"))
    )
    (net (code "103") (name "/PC5") (class "Default")
      (node (ref "IC3") (pin "45") (pinfunction "PC5_45") (pintype "bidirectional"))
      (node (ref "JP1") (pin "10") (pinfunction "10_10") (pintype "passive"))
    )
    (net (code "104") (name "/PC6") (class "Default")
      (node (ref "IC3") (pin "96") (pinfunction "PC6_96") (pintype "bidirectional"))
      (node (ref "JP3") (pin "9") (pinfunction "9_9") (pintype "passive"))
    )
    (net (code "105") (name "/PC7") (class "Default")
      (node (ref "IC3") (pin "97") (pinfunction "PC7_97") (pintype "bidirectional"))
      (node (ref "JP3") (pin "12") (pinfunction "12_12") (pintype "passive"))
    )
    (net (code "106") (name "/PC13_SD_DETECT") (class "Default")
      (node (ref "IC3") (pin "7") (pinfunction "PC13_7") (pintype "bidirectional"))
      (node (ref "X1") (pin "SWITCH") (pinfunction "SWITCH_SWITCH") (pintype "bidirectional"))
    )
    (net (code "107") (name "/PC14") (class "Default")
      (node (ref "IC3") (pin "8") (pinfunction "PC14/OSC32_IN_8") (pintype "bidirectional"))
      (node (ref "IC5") (pin "14") (pinfunction "RST_14") (pintype "bidirectional"))
    )
    (net (code "108") (name "/PC15") (class "Default")
      (node (ref "IC3") (pin "9") (pinfunction "PC15/OSC32_OUT_9") (pintype "bidirectional"))
      (node (ref "R62") (pin "2") (pinfunction "2_2") (pintype "passive"))
    )
    (net (code "109") (name "/PD7") (class "Default")
      (node (ref "IC3") (pin "123") (pinfunction "PD7_123") (pintype "bidirectional"))
      (node (ref "JP1") (pin "6") (pinfunction "6_6") (pintype "passive"))
    )
    (net (code "110") (name "/PD11") (class "Default")
      (node (ref "IC3") (pin "80") (pinfunction "PD11_80") (pintype "bidirectional"))
      (node (ref "JP3") (pin "8") (pinfunction "8_8") (pintype "passive"))
    )
    (net (code "111") (name "/PD12") (class "Default")
      (node (ref "IC3") (pin "81") (pinfunction "PD12_81") (pintype "bidirectional"))
      (node (ref "JP3") (pin "7") (pinfunction "7_7") (pintype "passive"))
    )
    (net (code "112") (name "/PD13") (class "Default")
      (node (ref "IC3") (pin "82") (pinfunction "PD13_82") (pintype "bidirectional"))
      (node (ref "JP3") (pin "10") (pinfunction "10_10") (pintype "passive"))
    )
    (net (code "113") (name "/PF6") (class "Default")
      (node (ref "IC3") (pin "18") (pinfunction "PF6_18") (pintype "bidirectional"))
      (node (ref "JP1") (pin "21") (pinfunction "21_21") (pintype "passive"))
    )
    (net (code "114") (name "/PF7") (class "Default")
      (node (ref "IC3") (pin "19") (pinfunction "PF7_19") (pintype "bidirectional"))
      (node (ref "JP1") (pin "22") (pinfunction "22_22") (pintype "passive"))
    )
    (net (code "115") (name "/PF8") (class "Default")
      (node (ref "IC3") (pin "20") (pinfunction "PF8_20") (pintype "bidirectional"))
      (node (ref "JP1") (pin "23") (pinfunction "23_23") (pintype "passive"))
    )
    (net (code "116") (name "/PF9") (class "Default")
      (node (ref "IC3") (pin "21") (pinfunction "PF9_21") (pintype "bidirectional"))
      (node (ref "JP1") (pin "24") (pinfunction "24_24") (pintype "passive"))
    )
    (net (code "117") (name "/PF10") (class "Default")
      (node (ref "IC3") (pin "22") (pinfunction "PF10_22") (pintype "bidirectional"))
      (node (ref "JP1") (pin "25") (pinfunction "25_25") (pintype "passive"))
    )
    (net (code "118") (name "/PG6") (class "Default")
      (node (ref "IC3") (pin "91") (pinfunction "PG6_91") (pintype "bidirectional"))
      (node (ref "JP3") (pin "11") (pinfunction "11_11") (pintype "passive"))
    )
    (net (code "119") (name "/PG7") (class "Default")
      (node (ref "IC3") (pin "92") (pinfunction "PG7_92") (pintype "bidirectional"))
      (node (ref "JP3") (pin "14") (pinfunction "14_14") (pintype "passive"))
    )
    (net (code "120") (name "/PG9") (class "Default")
      (node (ref "IC3") (pin "124") (pinfunction "PG9_124") (pintype "bidirectional"))
      (node (ref "JP1") (pin "5") (pinfunction "5_5") (pintype "passive"))
    )
    (net (code "121") (name "/PG10") (class "Default")
      (node (ref "IC3") (pin "125") (pinfunction "PG10_125") (pintype "bidirectional"))
      (node (ref "JP1") (pin "4") (pinfunction "4_4") (pintype "passive"))
    )
    (net (code "122") (name "/PG11") (class "Default")
      (node (ref "IC3") (pin "126") (pinfunction "PG11_126") (pintype "bidirectional"))
      (node (ref "JP1") (pin "3") (pinfunction "3_3") (pintype "passive"))
    )
    (net (code "123") (name "/RAS-R") (class "Default")
      (node (ref "IC2") (pin "18") (pinfunction "RAS#_18") (pintype "input"))
      (node (ref "R58") (pin "2") (pinfunction "2_2") (pintype "passive"))
    )
    (net (code "124") (name "/RAS-S") (class "Default")
      (node (ref "IC3") (pin "49") (pinfunction "PF11_49") (pintype "bidirectional"))
      (node (ref "R58") (pin "1") (pinfunction "1_1") (pintype "passive"))
    )
    (net (code "125") (name "/SAI1_FS_A") (class "Default")
      (node (ref "IC3") (pin "3") (pinfunction "PE4_3") (pintype "bidirectional"))
      (node (ref "IC5") (pin "4") (pinfunction "LRCK_4") (pintype "bidirectional"))
      (node (ref "R62") (pin "1") (pinfunction "1_1") (pintype "passive"))
    )
    (net (code "126") (name "/SAI1_MCLK_A") (class "Default")
      (node (ref "IC3") (pin "1") (pinfunction "PE2_1") (pintype "bidirectional"))
      (node (ref "IC5") (pin "3") (pinfunction "MCLK_3") (pintype "bidirectional"))
    )
    (net (code "127") (name "/SAI1_SCK_A") (class "Default")
      (node (ref "IC3") (pin "4") (pinfunction "PE5_4") (pintype "bidirectional"))
      (node (ref "IC5") (pin "5") (pinfunction "SCLK_5") (pintype "bidirectional"))
    )
    (net (code "128") (name "/SAI1_SD_A") (class "Default")
      (node (ref "IC3") (pin "5") (pinfunction "PE6_5") (pintype "bidirectional"))
      (node (ref "IC5") (pin "7") (pinfunction "SDIN_7") (pintype "bidirectional"))
    )
    (net (code "129") (name "/SAI1_SD_B") (class "Default")
      (node (ref "IC3") (pin "2") (pinfunction "PE3_2") (pintype "bidirectional"))
      (node (ref "IC5") (pin "6") (pinfunction "SDOUT_6") (pintype "bidirectional"))
    )
    (net (code "130") (name "/SD_CLK") (class "Default")
      (node (ref "IC3") (pin "113") (pinfunction "PC12_113") (pintype "bidirectional"))
      (node (ref "R37") (pin "1") (pinfunction "1_1") (pintype "passive"))
    )
    (net (code "131") (name "/SD_CMD") (class "Default")
      (node (ref "IC3") (pin "116") (pinfunction "PD2_116") (pintype "bidirectional"))
      (node (ref "R35") (pin "1") (pinfunction "1_1") (pintype "passive"))
    )
    (net (code "132") (name "/SD_DAT0") (class "Default")
      (node (ref "IC3") (pin "98") (pinfunction "PC8_98") (pintype "bidirectional"))
      (node (ref "R38") (pin "1") (pinfunction "1_1") (pintype "passive"))
    )
    (net (code "133") (name "/SD_DAT1") (class "Default")
      (node (ref "IC3") (pin "99") (pinfunction "PC9_99") (pintype "bidirectional"))
      (node (ref "R39") (pin "1") (pinfunction "1_1") (pintype "passive"))
    )
    (net (code "134") (name "/SD_DAT2") (class "Default")
      (node (ref "IC3") (pin "111") (pinfunction "PC10_111") (pintype "bidirectional"))
      (node (ref "R9") (pin "1") (pinfunction "1_1") (pintype "passive"))
    )
    (net (code "135") (name "/SD_DAT3") (class "Default")
      (node (ref "IC3") (pin "112") (pinfunction "PC11_112") (pintype "bidirectional"))
      (node (ref "R34") (pin "1") (pinfunction "1_1") (pintype "passive"))
    )
    (net (code "136") (name "/SWCLK") (class "Default")
      (node (ref "IC3") (pin "109") (pinfunction "PA14(JTCK/SWCLK)_109") (pintype "bidirectional"))
      (node (ref "JP5") (pin "2") (pinfunction "2_2") (pintype "passive"))
      (node (ref "X2") (pin "4") (pinfunction "4_4") (pintype "bidirectional"))
    )
    (net (code "137") (name "/SWDIO") (class "Default")
      (node (ref "IC3") (pin "105") (pinfunction "PA13(JTMS-SWDIO)_105") (pintype "bidirectional"))
      (node (ref "JP5") (pin "4") (pinfunction "4_4") (pintype "passive"))
      (node (ref "X2") (pin "2") (pinfunction "2_2") (pintype "bidirectional"))
    )
    (net (code "138") (name "/SWDRESET") (class "Default")
      (node (ref "C5") (pin "1") (pinfunction "1_1") (pintype "passive"))
      (node (ref "IC3") (pin "25") (pinfunction "~{RST}_25") (pintype "bidirectional"))
      (node (ref "JP5") (pin "1") (pinfunction "1_1") (pintype "passive"))
      (node (ref "X2") (pin "10") (pinfunction "10_10") (pintype "bidirectional"))
    )
    (net (code "139") (name "/SWO") (class "Default")
      (node (ref "IC3") (pin "133") (pinfunction "PB3(JTDO/TRACESWO)_133") (pintype "bidirectional"))
      (node (ref "JP5") (pin "3") (pinfunction "3_3") (pintype "passive"))
      (node (ref "X2") (pin "6") (pinfunction "6_6") (pintype "bidirectional"))
    )
    (net (code "140") (name "/UD-R") (class "Default")
      (node (ref "IC2") (pin "39") (pinfunction "UDQM_39") (pintype "input"))
      (node (ref "R54") (pin "2") (pinfunction "2_2") (pintype "passive"))
    )
    (net (code "141") (name "/UD-S") (class "Default")
      (node (ref "IC3") (pin "142") (pinfunction "PE1_142") (pintype "bidirectional"))
      (node (ref "R54") (pin "1") (pinfunction "1_1") (pintype "passive"))
    )
    (net (code "142") (name "/WE-R") (class "Default")
      (node (ref "IC2") (pin "16") (pinfunction "WE#_16") (pintype "input"))
      (node (ref "R56") (pin "2") (pinfunction "2_2") (pintype "passive"))
    )
    (net (code "143") (name "/WE-S") (class "Default")
      (node (ref "IC3") (pin "26") (pinfunction "PC0_26") (pintype "bidirectional"))
      (node (ref "R56") (pin "1") (pinfunction "1_1") (pintype "passive"))
    )
    (net (code "144") (name "3V3") (class "Default")
      (node (ref "3V3A") (pin "1") (pinfunction "1_1") (pintype "passive"))
      (node (ref "C1") (pin "1") (pinfunction "1_1") (pintype "passive"))
      (node (ref "C2") (pin "1") (pinfunction "1_1") (pintype "passive"))
      (node (ref "C3") (pin "+") (pinfunction "+_+") (pintype "passive"))
      (node (ref "C6") (pin "1") (pinfunction "1_1") (pintype "passive"))
      (node (ref "C65") (pin "1") (pinfunction "1_1") (pintype "passive"))
      (node (ref "C71") (pin "1") (pinfunction "1_1") (pintype "passive"))
      (node (ref "IC3") (pin "33") (pinfunction "VDDA_33") (pintype "power_in"))
      (node (ref "IC9") (pin "1") (pinfunction "VOUT_1") (pintype "bidirectional"))
      (node (ref "JP1") (pin "20") (pinfunction "20_20") (pintype "passive"))
      (node (ref "R4") (pin "1") (pinfunction "1_1") (pintype "passive"))
    )
    (net (code "145") (name "5V0") (class "Default")
      (node (ref "5VA") (pin "1") (pinfunction "1_1") (pintype "passive"))
      (node (ref "C40") (pin "1") (pinfunction "1_1") (pintype "passive"))
      (node (ref "C41") (pin "1") (pinfunction "1_1") (pintype "passive"))
      (node (ref "C45") (pin "+") (pinfunction "+_+") (pintype "passive"))
      (node (ref "C46") (pin "1") (pinfunction "1_1") (pintype "passive"))
      (node (ref "C50") (pin "1") (pinfunction "1_1") (pintype "passive"))
      (node (ref "C51") (pin "1") (pinfunction "1_1") (pintype "passive"))
      (node (ref "C70") (pin "1") (pinfunction "1_1") (pintype "passive"))
      (node (ref "C72") (pin "1") (pinfunction "1_1") (pintype "passive"))
      (node (ref "C74") (pin "1") (pinfunction "1_1") (pintype "passive"))
      (node (ref "C75") (pin "1") (pinfunction "1_1") (pintype "passive"))
      (node (ref "C8") (pin "1") (pinfunction "1_1") (pintype "passive"))
      (node (ref "C9") (pin "1") (pinfunction "1_1") (pintype "passive"))
      (node (ref "IC1") (pin "4") (pinfunction "V+_4") (pintype "power_in"))
      (node (ref "IC5") (pin "20") (pinfunction "VA_20") (pintype "bidirectional"))
      (node (ref "IC6") (pin "5") (pinfunction "V+_5") (pintype "bidirectional"))
      (node (ref "IC8") (pin "1") (pinfunction "VOUT_1") (pintype "bidirectional"))
    )
    (net (code "146") (name "12V0") (class "Default")
      (node (ref "C37") (pin "1") (pinfunction "1_1") (pintype "passive"))
      (node (ref "IC7") (pin "5") (pinfunction "VOUT_5") (pintype "bidirectional"))
      (node (ref "IC8") (pin "4") (pinfunction "EN_4") (pintype "bidirectional"))
      (node (ref "IC8") (pin "6") (pinfunction "IN_6") (pintype "bidirectional"))
      (node (ref "R1") (pin "1") (pinfunction "1_1") (pintype "passive"))
    )
    (net (code "147") (name "AGND") (class "Default")
      (node (ref "AGND") (pin "1") (pinfunction "1_1") (pintype "passive"))
      (node (ref "AGND2") (pin "1") (pinfunction "1_1") (pintype "passive"))
      (node (ref "C1") (pin "2") (pinfunction "2_2") (pintype "passive"))
      (node (ref "C11") (pin "2") (pinfunction "2_2") (pintype "passive"))
      (node (ref "C2") (pin "2") (pinfunction "2_2") (pintype "passive"))
      (node (ref "C22") (pin "2") (pinfunction "2_2") (pintype "passive"))
      (node (ref "C24") (pin "-") (pinfunction "-_-") (pintype "passive"))
      (node (ref "C25") (pin "2") (pinfunction "2_2") (pintype "passive"))
      (node (ref "C26") (pin "2") (pinfunction "2_2") (pintype "passive"))
      (node (ref "C28") (pin "2") (pinfunction "2_2") (pintype "passive"))
      (node (ref "C3") (pin "-") (pinfunction "-_-") (pintype "passive"))
      (node (ref "C31") (pin "2") (pinfunction "2_2") (pintype "passive"))
      (node (ref "C33") (pin "2") (pinfunction "2_2") (pintype "passive"))
      (node (ref "C34") (pin "2") (pinfunction "2_2") (pintype "passive"))
      (node (ref "C35") (pin "-") (pinfunction "-_-") (pintype "passive"))
      (node (ref "C4") (pin "2") (pinfunction "2_2") (pintype "passive"))
      (node (ref "C40") (pin "2") (pinfunction "2_2") (pintype "passive"))
      (node (ref "C41") (pin "2") (pinfunction "2_2") (pintype "passive"))
      (node (ref "C45") (pin "-") (pinfunction "-_-") (pintype "passive"))
      (node (ref "C46") (pin "2") (pinfunction "2_2") (pintype "passive"))
      (node (ref "C50") (pin "2") (pinfunction "2_2") (pintype "passive"))
      (node (ref "C51") (pin "2") (pinfunction "2_2") (pintype "passive"))
      (node (ref "C54") (pin "-") (pinfunction "-_-") (pintype "passive"))
      (node (ref "C6") (pin "2") (pinfunction "2_2") (pintype "passive"))
      (node (ref "C64") (pin "2") (pinfunction "2_2") (pintype "passive"))
      (node (ref "C65") (pin "2") (pinfunction "2_2") (pintype "passive"))
      (node (ref "C70") (pin "2") (pinfunction "2_2") (pintype "passive"))
      (node (ref "C71") (pin "2") (pinfunction "2_2") (pintype "passive"))
      (node (ref "C72") (pin "2") (pinfunction "2_2") (pintype "passive"))
      (node (ref "C73") (pin "2") (pinfunction "2_2") (pintype "passive"))
      (node (ref "C74") (pin "2") (pinfunction "2_2") (pintype "passive"))
      (node (ref "C75") (pin "2") (pinfunction "2_2") (pintype "passive"))
      (node (ref "C8") (pin "2") (pinfunction "2_2") (pintype "passive"))
      (node (ref "C9") (pin "2") (pinfunction "2_2") (pintype "passive"))
      (node (ref "IC1") (pin "11") (pinfunction "V-_11") (pintype "power_in"))
      (node (ref "IC3") (pin "31") (pinfunction "VSSA_31") (pintype "power_in"))
      (node (ref "IC5") (pin "13") (pinfunction "AD0/CS_13") (pintype "bidirectional"))
      (node (ref "IC5") (pin "21") (pinfunction "AGND_21") (pintype "bidirectional"))
      (node (ref "IC6") (pin "2") (pinfunction "V-_2") (pintype "bidirectional"))
      (node (ref "IC8") (pin "5") (pinfunction "GND_5") (pintype "bidirectional"))
      (node (ref "IC8") (pin "PAD") (pinfunction "PAD_PAD") (pintype "bidirectional"))
      (node (ref "IC9") (pin "5") (pinfunction "GND_5") (pintype "bidirectional"))
      (node (ref "IC9") (pin "PAD") (pinfunction "PAD_PAD") (pintype "bidirectional"))
      (node (ref "JP1") (pin "19") (pinfunction "19_19") (pintype "passive"))
      (node (ref "JP2") (pin "3") (pinfunction "3_3") (pintype "passive"))
      (node (ref "JP2") (pin "4") (pinfunction "4_4") (pintype "passive"))
      (node (ref "JP2") (pin "5") (pinfunction "5_5") (pintype "passive"))
      (node (ref "JP2") (pin "6") (pinfunction "6_6") (pintype "passive"))
      (node (ref "R19") (pin "1") (pinfunction "1_1") (pintype "passive"))
      (node (ref "R27") (pin "1") (pinfunction "1_1") (pintype "passive"))
      (node (ref "R3") (pin "2") (pinfunction "2_2") (pintype "passive"))
    )
    (net (code "148") (name "DGND") (class "Default")
      (node (ref "C12") (pin "2") (pinfunction "2_2") (pintype "passive"))
      (node (ref "C13") (pin "2") (pinfunction "2_2") (pintype "passive"))
      (node (ref "C14") (pin "2") (pinfunction "2_2") (pintype "passive"))
      (node (ref "C15") (pin "2") (pinfunction "2_2") (pintype "passive"))
      (node (ref "C16") (pin "2") (pinfunction "2_2") (pintype "passive"))
      (node (ref "C17") (pin "2") (pinfunction "2_2") (pintype "passive"))
      (node (ref "C18") (pin "2") (pinfunction "2_2") (pintype "passive"))
      (node (ref "C19") (pin "2") (pinfunction "2_2") (pintype "passive"))
      (node (ref "C20") (pin "2") (pinfunction "2_2") (pintype "passive"))
      (node (ref "C32") (pin "2") (pinfunction "2_2") (pintype "passive"))
      (node (ref "C36") (pin "-") (pinfunction "-_-") (pintype "passive"))
      (node (ref "C37") (pin "2") (pinfunction "2_2") (pintype "passive"))
      (node (ref "C42") (pin "2") (pinfunction "2_2") (pintype "passive"))
      (node (ref "C43") (pin "2") (pinfunction "2_2") (pintype "passive"))
      (node (ref "C44") (pin "-") (pinfunction "-_-") (pintype "passive"))
      (node (ref "C47") (pin "2") (pinfunction "2_2") (pintype "passive"))
      (node (ref "C48") (pin "2") (pinfunction "2_2") (pintype "passive"))
      (node (ref "C49") (pin "2") (pinfunction "2_2") (pintype "passive"))
      (node (ref "C5") (pin "2") (pinfunction "2_2") (pintype "passive"))
      (node (ref "C55") (pin "2") (pinfunction "2_2") (pintype "passive"))
      (node (ref "C56") (pin "2") (pinfunction "2_2") (pintype "passive"))
      (node (ref "C57") (pin "2") (pinfunction "2_2") (pintype "passive"))
      (node (ref "C58") (pin "2") (pinfunction "2_2") (pintype "passive"))
      (node (ref "C59") (pin "2") (pinfunction "2_2") (pintype "passive"))
      (node (ref "C60") (pin "2") (pinfunction "2_2") (pintype "passive"))
      (node (ref "C61") (pin "2") (pinfunction "2_2") (pintype "passive"))
      (node (ref "C62") (pin "-") (pinfunction "-_-") (pintype "passive"))
      (node (ref "C63") (pin "2") (pinfunction "2_2") (pintype "passive"))
      (node (ref "C66") (pin "2") (pinfunction "2_2") (pintype "passive"))
      (node (ref "C67") (pin "2") (pinfunction "2_2") (pintype "passive"))
      (node (ref "C68") (pin "2") (pinfunction "2_2") (pintype "passive"))
      (node (ref "C69") (pin "2") (pinfunction "2_2") (pintype "passive"))
      (node (ref "C7") (pin "2") (pinfunction "2_2") (pintype "passive"))
      (node (ref "C76") (pin "2") (pinfunction "2_2") (pintype "passive"))
      (node (ref "C77") (pin "2") (pinfunction "2_2") (pintype "passive"))
      (node (ref "C78") (pin "2") (pinfunction "2_2") (pintype "passive"))
      (node (ref "C79") (pin "2") (pinfunction "2_2") (pintype "passive"))
      (node (ref "C80") (pin "2") (pinfunction "2_2") (pintype "passive"))
      (node (ref "DGND") (pin "1") (pinfunction "1_1") (pintype "passive"))
      (node (ref "DGND1") (pin "1") (pinfunction "1_1") (pintype "passive"))
      (node (ref "IC2") (pin "12") (pinfunction "VSSQ_12") (pintype "power_in"))
      (node (ref "IC2") (pin "28") (pinfunction "VSS_28") (pintype "power_in"))
      (node (ref "IC2") (pin "41") (pinfunction "VSS_41") (pintype "power_in"))
      (node (ref "IC2") (pin "46") (pinfunction "VSSQ_46") (pintype "power_in"))
      (node (ref "IC2") (pin "52") (pinfunction "VSSQ_52") (pintype "power_in"))
      (node (ref "IC2") (pin "54") (pinfunction "VSS_54") (pintype "power_in"))
      (node (ref "IC2") (pin "6") (pinfunction "VSSQ_6") (pintype "power_in"))
      (node (ref "IC3") (pin "107") (pinfunction "VSS_107") (pintype "power_in"))
      (node (ref "IC3") (pin "120") (pinfunction "VSS_120") (pintype "power_in"))
      (node (ref "IC3") (pin "130") (pinfunction "VSS_130") (pintype "power_in"))
      (node (ref "IC3") (pin "16") (pinfunction "VSS_16") (pintype "power_in"))
      (node (ref "IC3") (pin "38") (pinfunction "VSS_38") (pintype "power_in"))
      (node (ref "IC3") (pin "51") (pinfunction "VSS_51") (pintype "power_in"))
      (node (ref "IC3") (pin "61") (pinfunction "VSS_61") (pintype "power_in"))
      (node (ref "IC3") (pin "83") (pinfunction "VSS_83") (pintype "power_in"))
      (node (ref "IC3") (pin "94") (pinfunction "VSS_94") (pintype "power_in"))
      (node (ref "IC4") (pin "1") (pinfunction "GND_1") (pintype "bidirectional"))
      (node (ref "IC5") (pin "2") (pinfunction "XTI_2") (pintype "bidirectional"))
      (node (ref "IC5") (pin "8") (pinfunction "DGND_8") (pintype "bidirectional"))
      (node (ref "IC7") (pin "2") (pinfunction "GND_2") (pintype "bidirectional"))
      (node (ref "JP3") (pin "19") (pinfunction "19_19") (pintype "passive"))
      (node (ref "JP3") (pin "2") (pinfunction "2_2") (pintype "passive"))
      (node (ref "JP5") (pin "5") (pinfunction "5_5") (pintype "passive"))
      (node (ref "LED1") (pin "C") (pinfunction "C_C") (pintype "passive"))
      (node (ref "LED2") (pin "C") (pinfunction "C_C") (pintype "passive"))
      (node (ref "Q1") (pin "2") (pinfunction "G2_2") (pintype "power_in"))
      (node (ref "Q1") (pin "4") (pinfunction "G1_4") (pintype "power_in"))
      (node (ref "R2") (pin "2") (pinfunction "2_2") (pintype "passive"))
      (node (ref "R3") (pin "1") (pinfunction "1_1") (pintype "passive"))
      (node (ref "R5") (pin "2") (pinfunction "2_2") (pintype "passive"))
      (node (ref "X1") (pin "P6") (pinfunction "VSS_P6") (pintype "bidirectional"))
      (node (ref "X2") (pin "3") (pinfunction "3_3") (pintype "bidirectional"))
      (node (ref "X2") (pin "5") (pinfunction "5_5") (pintype "bidirectional"))
      (node (ref "X2") (pin "9") (pinfunction "9_9") (pintype "bidirectional"))
    )
    (net (code "149") (name "Net-(C4-Pad1)") (class "Default")
      (node (ref "C4") (pin "1") (pinfunction "1_1") (pintype "passive"))
      (node (ref "R12") (pin "2") (pinfunction "2_2") (pintype "passive"))
      (node (ref "R13") (pin "1") (pinfunction "1_1") (pintype "passive"))
      (node (ref "R17") (pin "1") (pinfunction "1_1") (pintype "passive"))
    )
    (net (code "150") (name "Net-(C10-Pad+)") (class "Default")
      (node (ref "C10") (pin "+") (pinfunction "+_+") (pintype "passive"))
      (node (ref "JP2") (pin "7") (pinfunction "7_7") (pintype "passive"))
    )
    (net (code "151") (name "Net-(C11-Pad1)") (class "Default")
      (node (ref "C11") (pin "1") (pinfunction "1_1") (pintype "passive"))
      (node (ref "R16") (pin "1") (pinfunction "1_1") (pintype "passive"))
      (node (ref "R7") (pin "2") (pinfunction "2_2") (pintype "passive"))
      (node (ref "R8") (pin "1") (pinfunction "1_1") (pintype "passive"))
    )
    (net (code "152") (name "Net-(C19-Pad1)") (class "Default")
      (node (ref "C19") (pin "1") (pinfunction "1_1") (pintype "passive"))
      (node (ref "IC3") (pin "106") (pinfunction "VCAP_106") (pintype "power_in"))
      (node (ref "IC3") (pin "71") (pinfunction "VCAP_71") (pintype "power_in"))
    )
    (net (code "153") (name "Net-(C23-Pad-)") (class "Default")
      (node (ref "C23") (pin "-") (pinfunction "-_-") (pintype "passive"))
      (node (ref "R18") (pin "1") (pinfunction "1_1") (pintype "passive"))
    )
    (net (code "154") (name "Net-(C24-Pad+)") (class "Default")
      (node (ref "C24") (pin "+") (pinfunction "+_+") (pintype "passive"))
      (node (ref "R24") (pin "2") (pinfunction "2_2") (pintype "passive"))
    )
    (net (code "155") (name "Net-(C25-Pad1)") (class "Default")
      (node (ref "C25") (pin "1") (pinfunction "1_1") (pintype "passive"))
      (node (ref "R22") (pin "2") (pinfunction "2_2") (pintype "passive"))
      (node (ref "R23") (pin "1") (pinfunction "1_1") (pintype "passive"))
      (node (ref "R25") (pin "1") (pinfunction "1_1") (pintype "passive"))
    )
    (net (code "156") (name "Net-(C26-Pad1)") (class "Default")
      (node (ref "C26") (pin "1") (pinfunction "1_1") (pintype "passive"))
      (node (ref "R20") (pin "2") (pinfunction "2_2") (pintype "passive"))
      (node (ref "R21") (pin "1") (pinfunction "1_1") (pintype "passive"))
      (node (ref "R24") (pin "1") (pinfunction "1_1") (pintype "passive"))
    )
    (net (code "157") (name "Net-(C29-Pad-)") (class "Default")
      (node (ref "C29") (pin "-") (pinfunction "-_-") (pintype "passive"))
      (node (ref "R26") (pin "1") (pinfunction "1_1") (pintype "passive"))
    )
    (net (code "158") (name "Net-(C30-Pad+)") (class "Default")
      (node (ref "C30") (pin "+") (pinfunction "+_+") (pintype "passive"))
      (node (ref "JP2") (pin "8") (pinfunction "8_8") (pintype "passive"))
    )
    (net (code "159") (name "Net-(C54-Pad+)") (class "Default")
      (node (ref "C54") (pin "+") (pinfunction "+_+") (pintype "passive"))
      (node (ref "R16") (pin "2") (pinfunction "2_2") (pintype "passive"))
    )
    (net (code "160") (name "Net-(IC1A-+IN)") (class "Default")
      (node (ref "C30") (pin "-") (pinfunction "-_-") (pintype "passive"))
      (node (ref "IC1") (pin "3") (pinfunction "+IN_3") (pintype "input"))
      (node (ref "R30") (pin "2") (pinfunction "2_2") (pintype "passive"))
    )
    (net (code "161") (name "Net-(IC1A--IN)") (class "Default")
      (node (ref "C38") (pin "2") (pinfunction "2_2") (pintype "passive"))
      (node (ref "IC1") (pin "2") (pinfunction "-IN_2") (pintype "input"))
      (node (ref "R29") (pin "1") (pinfunction "1_1") (pintype "passive"))
    )
    (net (code "162") (name "Net-(IC1A-OUT)") (class "Default")
      (node (ref "C38") (pin "1") (pinfunction "1_1") (pintype "passive"))
      (node (ref "IC1") (pin "1") (pinfunction "OUT_1") (pintype "output"))
      (node (ref "R28") (pin "1") (pinfunction "1_1") (pintype "passive"))
    )
    (net (code "163") (name "Net-(IC1B-+IN)") (class "Default")
      (node (ref "C10") (pin "-") (pinfunction "-_-") (pintype "passive"))
      (node (ref "IC1") (pin "5") (pinfunction "+IN_5") (pintype "input"))
      (node (ref "R31") (pin "1") (pinfunction "1_1") (pintype "passive"))
    )
    (net (code "164") (name "Net-(IC1B--IN)") (class "Default")
      (node (ref "C39") (pin "2") (pinfunction "2_2") (pintype "passive"))
      (node (ref "IC1") (pin "6") (pinfunction "-IN_6") (pintype "input"))
      (node (ref "R32") (pin "1") (pinfunction "1_1") (pintype "passive"))
    )
    (net (code "165") (name "Net-(IC1B-OUT)") (class "Default")
      (node (ref "C39") (pin "1") (pinfunction "1_1") (pintype "passive"))
      (node (ref "IC1") (pin "7") (pinfunction "OUT_7") (pintype "output"))
      (node (ref "R33") (pin "1") (pinfunction "1_1") (pintype "passive"))
    )
    (net (code "166") (name "Net-(IC1C-+IN)") (class "Default")
      (node (ref "C22") (pin "1") (pinfunction "1_1") (pintype "passive"))
      (node (ref "IC1") (pin "10") (pinfunction "+IN_10") (pintype "input"))
      (node (ref "R8") (pin "2") (pinfunction "2_2") (pintype "passive"))
    )
    (net (code "167") (name "Net-(IC1C--IN)") (class "Default")
      (node (ref "C21") (pin "1") (pinfunction "1_1") (pintype "passive"))
      (node (ref "IC1") (pin "9") (pinfunction "-IN_9") (pintype "input"))
      (node (ref "R13") (pin "2") (pinfunction "2_2") (pintype "passive"))
    )
    (net (code "168") (name "Net-(IC1C-OUT)") (class "Default")
      (node (ref "C21") (pin "2") (pinfunction "2_2") (pintype "passive"))
      (node (ref "C23") (pin "+") (pinfunction "+_+") (pintype "passive"))
      (node (ref "IC1") (pin "8") (pinfunction "OUT_8") (pintype "output"))
      (node (ref "R17") (pin "2") (pinfunction "2_2") (pintype "passive"))
    )
    (net (code "169") (name "Net-(IC1D-+IN)") (class "Default")
      (node (ref "C28") (pin "1") (pinfunction "1_1") (pintype "passive"))
      (node (ref "IC1") (pin "12") (pinfunction "+IN_12") (pintype "input"))
      (node (ref "R21") (pin "2") (pinfunction "2_2") (pintype "passive"))
    )
    (net (code "170") (name "Net-(IC1D--IN)") (class "Default")
      (node (ref "C27") (pin "1") (pinfunction "1_1") (pintype "passive"))
      (node (ref "IC1") (pin "13") (pinfunction "-IN_13") (pintype "input"))
      (node (ref "R23") (pin "2") (pinfunction "2_2") (pintype "passive"))
    )
    (net (code "171") (name "Net-(IC1D-OUT)") (class "Default")
      (node (ref "C27") (pin "2") (pinfunction "2_2") (pintype "passive"))
      (node (ref "C29") (pin "+") (pinfunction "+_+") (pintype "passive"))
      (node (ref "IC1") (pin "14") (pinfunction "OUT_14") (pintype "output"))
      (node (ref "R25") (pin "2") (pinfunction "2_2") (pintype "passive"))
    )
    (net (code "172") (name "Net-(IC3A-BOOT0)") (class "Default")
      (node (ref "IC3") (pin "138") (pinfunction "BOOT0_138") (pintype "input"))
      (node (ref "R5") (pin "1") (pinfunction "1_1") (pintype "passive"))
    )
    (net (code "173") (name "Net-(IC3A-PH0{slash}OSC_IN)") (class "Default")
      (node (ref "C17") (pin "1") (pinfunction "1_1") (pintype "passive"))
      (node (ref "IC3") (pin "23") (pinfunction "PH0/OSC_IN_23") (pintype "bidirectional"))
      (node (ref "Q1") (pin "1") (pinfunction "X1_1") (pintype "bidirectional"))
    )
    (net (code "174") (name "Net-(IC3A-PH1{slash}OSC_OUT)") (class "Default")
      (node (ref "C18") (pin "1") (pinfunction "1_1") (pintype "passive"))
      (node (ref "IC3") (pin "24") (pinfunction "PH1/OSC_OUT_24") (pintype "bidirectional"))
      (node (ref "Q1") (pin "3") (pinfunction "X2_3") (pintype "bidirectional"))
    )
    (net (code "175") (name "Net-(IC3A-VREF+)") (class "Default")
      (node (ref "C64") (pin "1") (pinfunction "1_1") (pintype "passive"))
      (node (ref "IC3") (pin "32") (pinfunction "VREF+_32") (pintype "power_in"))
      (node (ref "R4") (pin "2") (pinfunction "2_2") (pintype "passive"))
    )
    (net (code "176") (name "Net-(IC3B-PB4(~{JTRST}))") (class "Default")
      (node (ref "IC3") (pin "134") (pinfunction "PB4(~{JTRST})_134") (pintype "bidirectional"))
      (node (ref "R79") (pin "1") (pinfunction "1_1") (pintype "passive"))
    )
    (net (code "177") (name "Net-(IC3B-PB13)") (class "Default")
      (node (ref "IC3") (pin "74") (pinfunction "PB13_74") (pintype "bidirectional"))
      (node (ref "R14") (pin "2") (pinfunction "2_2") (pintype "passive"))
    )
    (net (code "178") (name "Net-(IC3B-PB15)") (class "Default")
      (node (ref "IC3") (pin "76") (pinfunction "PB15_76") (pintype "bidirectional"))
      (node (ref "R15") (pin "2") (pinfunction "2_2") (pintype "passive"))
    )
    (net (code "179") (name "Net-(IC5-AINA)") (class "Default")
      (node (ref "C52") (pin "1") (pinfunction "1_1") (pintype "passive"))
      (node (ref "IC5") (pin "17") (pinfunction "AINA_17") (pintype "bidirectional"))
      (node (ref "R28") (pin "2") (pinfunction "2_2") (pintype "passive"))
      (node (ref "R29") (pin "2") (pinfunction "2_2") (pintype "passive"))
    )
    (net (code "180") (name "Net-(IC5-AINB)") (class "Default")
      (node (ref "C53") (pin "2") (pinfunction "2_2") (pintype "passive"))
      (node (ref "IC5") (pin "18") (pinfunction "AINB_18") (pintype "bidirectional"))
      (node (ref "R32") (pin "2") (pinfunction "2_2") (pintype "passive"))
      (node (ref "R33") (pin "2") (pinfunction "2_2") (pintype "passive"))
    )
    (net (code "181") (name "Net-(IC5-AOUTA+)") (class "Default")
      (node (ref "IC5") (pin "25") (pinfunction "AOUTA+_25") (pintype "bidirectional"))
      (node (ref "R20") (pin "1") (pinfunction "1_1") (pintype "passive"))
    )
    (net (code "182") (name "Net-(IC5-AOUTA-)") (class "Default")
      (node (ref "IC5") (pin "24") (pinfunction "AOUTA-_24") (pintype "bidirectional"))
      (node (ref "R22") (pin "1") (pinfunction "1_1") (pintype "passive"))
    )
    (net (code "183") (name "Net-(IC5-AOUTB+)") (class "Default")
      (node (ref "IC5") (pin "26") (pinfunction "AOUTB+_26") (pintype "bidirectional"))
      (node (ref "R7") (pin "1") (pinfunction "1_1") (pintype "passive"))
    )
    (net (code "184") (name "Net-(IC5-AOUTB-)") (class "Default")
      (node (ref "IC5") (pin "27") (pinfunction "AOUTB-_27") (pintype "bidirectional"))
      (node (ref "R12") (pin "1") (pinfunction "1_1") (pintype "passive"))
    )
    (net (code "185") (name "Net-(IC5-FILT+)") (class "Default")
      (node (ref "C31") (pin "1") (pinfunction "1_1") (pintype "passive"))
      (node (ref "C35") (pin "+") (pinfunction "+_+") (pintype "passive"))
      (node (ref "IC5") (pin "22") (pinfunction "FILT+_22") (pintype "bidirectional"))
    )
    (net (code "186") (name "Net-(IC5-VQ1)") (class "Default")
      (node (ref "C33") (pin "1") (pinfunction "1_1") (pintype "passive"))
      (node (ref "C34") (pin "1") (pinfunction "1_1") (pintype "passive"))
      (node (ref "IC5") (pin "15") (pinfunction "VQ1_15") (pintype "bidirectional"))
      (node (ref "IC6") (pin "3") (pinfunction "IN+_3") (pintype "bidirectional"))
    )
    (net (code "187") (name "Net-(IC5-VQ2)") (class "Default")
      (node (ref "C52") (pin "2") (pinfunction "2_2") (pintype "passive"))
      (node (ref "C53") (pin "1") (pinfunction "1_1") (pintype "passive"))
      (node (ref "C73") (pin "1") (pinfunction "1_1") (pintype "passive"))
      (node (ref "IC5") (pin "16") (pinfunction "VQ2_16") (pintype "bidirectional"))
      (node (ref "IC5") (pin "19") (pinfunction "VQ3_19") (pintype "bidirectional"))
      (node (ref "IC6") (pin "1") (pinfunction "OUT_1") (pintype "bidirectional"))
      (node (ref "IC6") (pin "4") (pinfunction "IN-_4") (pintype "bidirectional"))
      (node (ref "R30") (pin "1") (pinfunction "1_1") (pintype "passive"))
      (node (ref "R31") (pin "2") (pinfunction "2_2") (pintype "passive"))
    )
    (net (code "188") (name "Net-(IC7-FB)") (class "Default")
      (node (ref "IC7") (pin "4") (pinfunction "FB_4") (pintype "bidirectional"))
      (node (ref "R1") (pin "2") (pinfunction "2_2") (pintype "passive"))
      (node (ref "R2") (pin "1") (pinfunction "1_1") (pintype "passive"))
    )
    (net (code "189") (name "Net-(IC7-SW)") (class "Default")
      (node (ref "IC7") (pin "6") (pinfunction "SW_6") (pintype "bidirectional"))
      (node (ref "L1") (pin "P$2") (pinfunction "P$2_P$2") (pintype "bidirectional"))
    )
    (net (code "190") (name "Net-(JP2-Pad1)") (class "Default")
      (node (ref "JP2") (pin "1") (pinfunction "1_1") (pintype "passive"))
      (node (ref "R18") (pin "2") (pinfunction "2_2") (pintype "passive"))
      (node (ref "R19") (pin "2") (pinfunction "2_2") (pintype "passive"))
    )
    (net (code "191") (name "Net-(JP2-Pad2)") (class "Default")
      (node (ref "JP2") (pin "2") (pinfunction "2_2") (pintype "passive"))
      (node (ref "R26") (pin "2") (pinfunction "2_2") (pintype "passive"))
      (node (ref "R27") (pin "2") (pinfunction "2_2") (pintype "passive"))
    )
    (net (code "192") (name "Net-(LED1-PadA)") (class "Default")
      (node (ref "LED1") (pin "A") (pinfunction "A_A") (pintype "passive"))
      (node (ref "R6") (pin "2") (pinfunction "2_2") (pintype "passive"))
    )
    (net (code "193") (name "Net-(LED2-PadA)") (class "Default")
      (node (ref "LED2") (pin "A") (pinfunction "A_A") (pintype "passive"))
      (node (ref "R79") (pin "2") (pinfunction "2_2") (pintype "passive"))
    )
    (net (code "194") (name "Net-(X1-CLK)") (class "Default")
      (node (ref "R37") (pin "2") (pinfunction "2_2") (pintype "passive"))
      (node (ref "X1") (pin "P5") (pinfunction "CLK_P5") (pintype "bidirectional"))
    )
    (net (code "195") (name "Net-(X1-CMD)") (class "Default")
      (node (ref "R35") (pin "2") (pinfunction "2_2") (pintype "passive"))
      (node (ref "X1") (pin "P3") (pinfunction "CMD_P3") (pintype "bidirectional"))
    )
    (net (code "196") (name "Net-(X1-DAT0)") (class "Default")
      (node (ref "R38") (pin "2") (pinfunction "2_2") (pintype "passive"))
      (node (ref "X1") (pin "P7") (pinfunction "DAT0_P7") (pintype "bidirectional"))
    )
    (net (code "197") (name "Net-(X1-DAT1)") (class "Default")
      (node (ref "R39") (pin "2") (pinfunction "2_2") (pintype "passive"))
      (node (ref "X1") (pin "P8") (pinfunction "DAT1_P8") (pintype "bidirectional"))
    )
    (net (code "198") (name "Net-(X1-DAT2)") (class "Default")
      (node (ref "R9") (pin "2") (pinfunction "2_2") (pintype "passive"))
      (node (ref "X1") (pin "P1") (pinfunction "DAT2_P1") (pintype "bidirectional"))
    )
    (net (code "199") (name "Net-(X1-DAT3)") (class "Default")
      (node (ref "R34") (pin "2") (pinfunction "2_2") (pintype "passive"))
      (node (ref "X1") (pin "P2") (pinfunction "DAT3_P2") (pintype "bidirectional"))
    )
    (net (code "200") (name "unconnected-(IC2-NC1-Pad40)") (class "Default")
      (node (ref "IC2") (pin "40") (pinfunction "NC1_40") (pintype "no_connect"))
    )
    (net (code "201") (name "unconnected-(IC3A-PA15(JTDI)-Pad110)") (class "Default")
      (node (ref "IC3") (pin "110") (pinfunction "PA15(JTDI)_110") (pintype "bidirectional"))
    )
    (net (code "202") (name "unconnected-(IC3B-PB2-Pad48)") (class "Default")
      (node (ref "IC3") (pin "48") (pinfunction "PB2_48") (pintype "bidirectional"))
    )
    (net (code "203") (name "unconnected-(IC3C-PD3-Pad117)") (class "Default")
      (node (ref "IC3") (pin "117") (pinfunction "PD3_117") (pintype "bidirectional"))
    )
    (net (code "204") (name "unconnected-(IC3C-PD4-Pad118)") (class "Default")
      (node (ref "IC3") (pin "118") (pinfunction "PD4_118") (pintype "bidirectional"))
    )
    (net (code "205") (name "unconnected-(IC3C-PD5-Pad119)") (class "Default")
      (node (ref "IC3") (pin "119") (pinfunction "PD5_119") (pintype "bidirectional"))
    )
    (net (code "206") (name "unconnected-(IC3C-PD6-Pad122)") (class "Default")
      (node (ref "IC3") (pin "122") (pinfunction "PD6_122") (pintype "bidirectional"))
    )
    (net (code "207") (name "unconnected-(IC3D-PG3-Pad88)") (class "Default")
      (node (ref "IC3") (pin "88") (pinfunction "PG3_88") (pintype "bidirectional"))
    )
    (net (code "208") (name "unconnected-(IC3D-PG12-Pad127)") (class "Default")
      (node (ref "IC3") (pin "127") (pinfunction "PG12_127") (pintype "bidirectional"))
    )
    (net (code "209") (name "unconnected-(IC3D-PG13-Pad128)") (class "Default")
      (node (ref "IC3") (pin "128") (pinfunction "PG13_128") (pintype "bidirectional"))
    )
    (net (code "210") (name "unconnected-(IC3D-PG14-Pad129)") (class "Default")
      (node (ref "IC3") (pin "129") (pinfunction "PG14_129") (pintype "bidirectional"))
    )
    (net (code "211") (name "unconnected-(IC5-AMUTEC-Pad23)") (class "Default")
      (node (ref "IC5") (pin "23") (pinfunction "AMUTEC_23") (pintype "bidirectional"))
    )
    (net (code "212") (name "unconnected-(IC5-BMUTEC-Pad28)") (class "Default")
      (node (ref "IC5") (pin "28") (pinfunction "BMUTEC_28") (pintype "bidirectional"))
    )
    (net (code "213") (name "unconnected-(IC5-XTO-Pad1)") (class "Default")
      (node (ref "IC5") (pin "1") (pinfunction "XTO_1") (pintype "bidirectional"))
    )
    (net (code "214") (name "unconnected-(IC8-PG-Pad3)") (class "Default")
      (node (ref "IC8") (pin "3") (pinfunction "PG_3") (pintype "bidirectional"))
    )
    (net (code "215") (name "unconnected-(IC9-PG-Pad3)") (class "Default")
      (node (ref "IC9") (pin "3") (pinfunction "PG_3") (pintype "bidirectional"))
    )
    (net (code "216") (name "unconnected-(JP5-Pad6)") (class "Default")
      (node (ref "JP5") (pin "6") (pinfunction "6_6") (pintype "passive"))
    )
    (net (code "217") (name "unconnected-(X2-Pad7)") (class "Default")
      (node (ref "X2") (pin "7") (pinfunction "7_7") (pintype "bidirectional"))
    )
    (net (code "218") (name "unconnected-(X2-Pad8)") (class "Default")
      (node (ref "X2") (pin "8") (pinfunction "8_8") (pintype "bidirectional"))
    )
  )
)
